# PCB0M3_2C.net
KiCad netlist of a schematic drawn in EAGLE
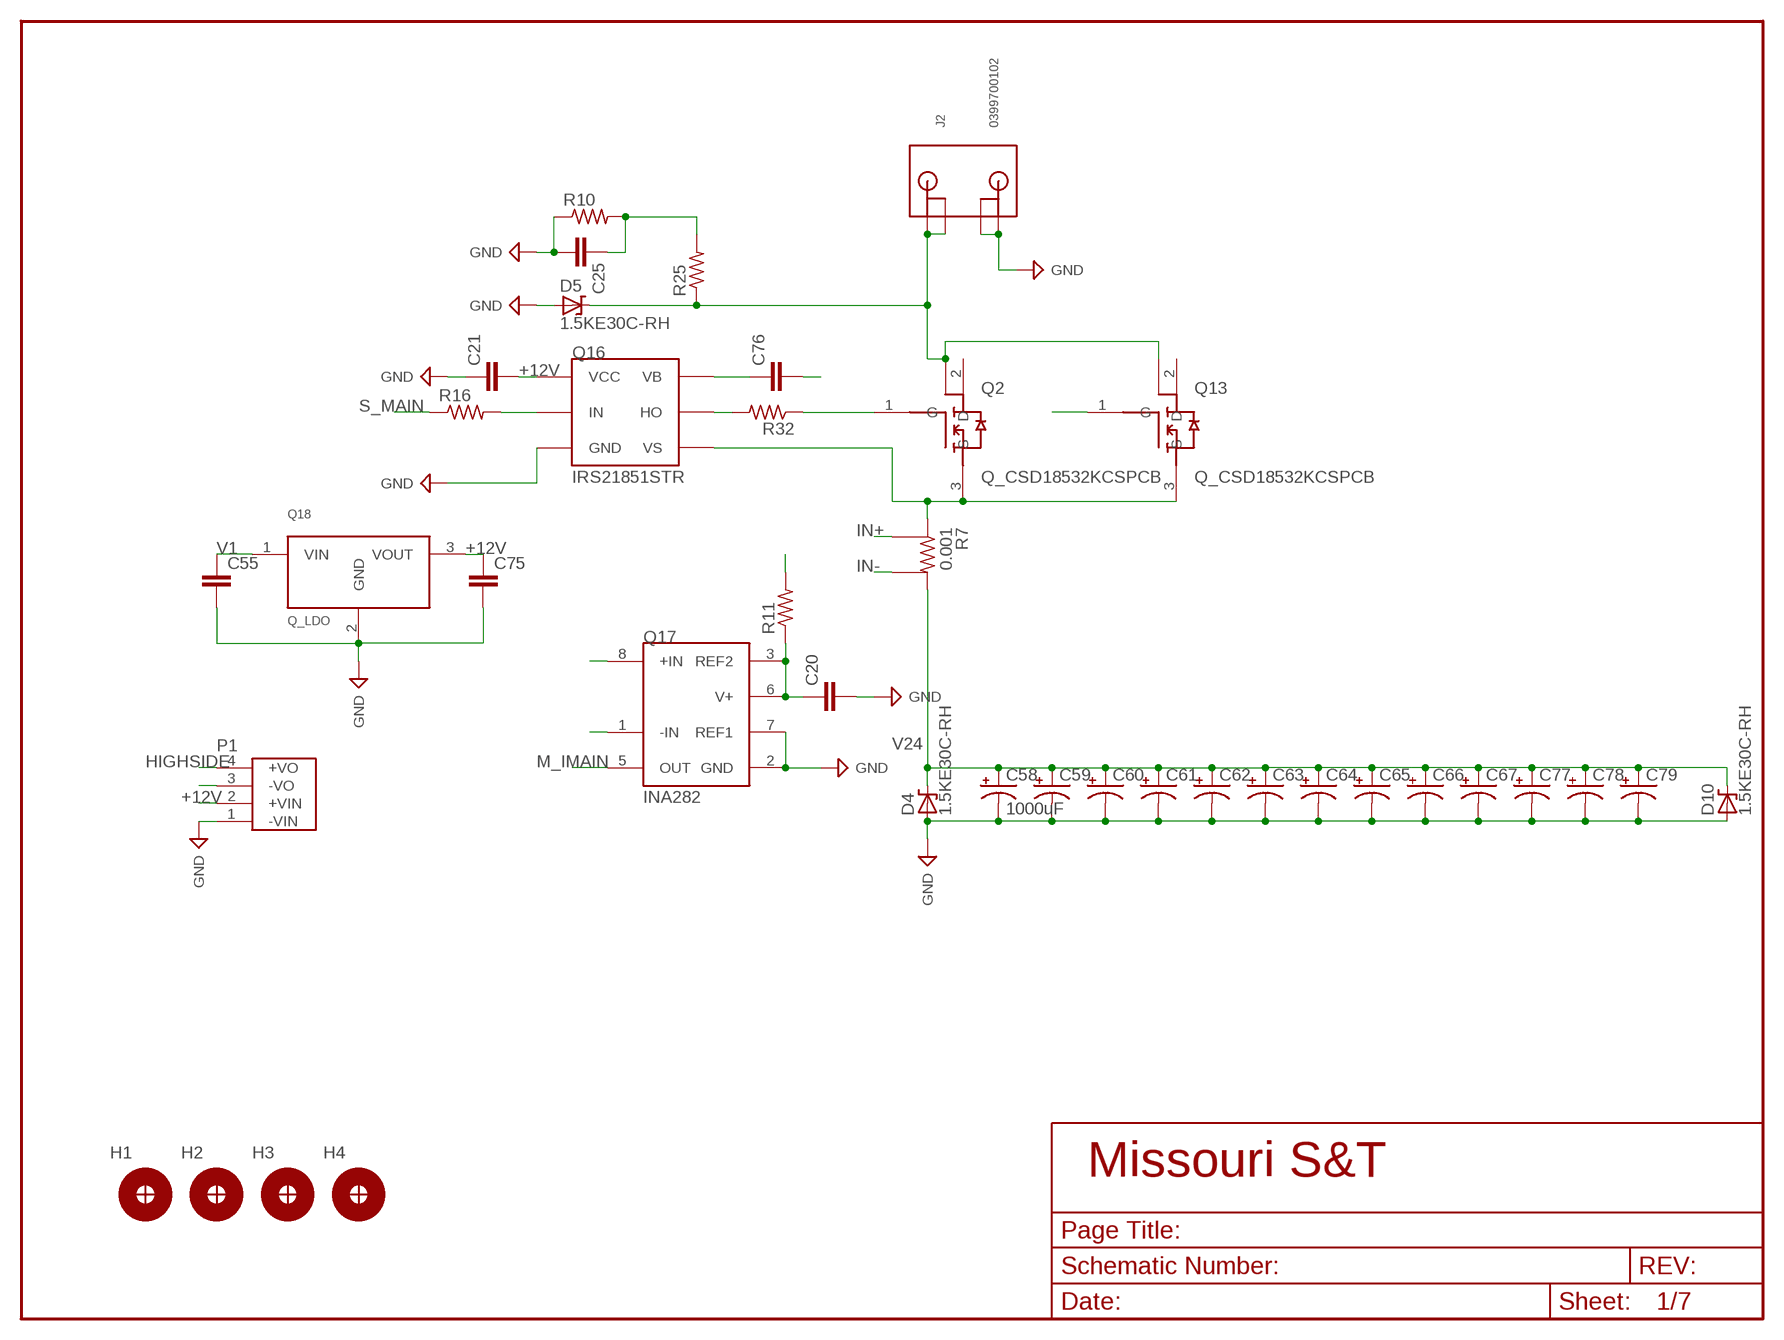
[diagram p0: schematic, sheet 1]
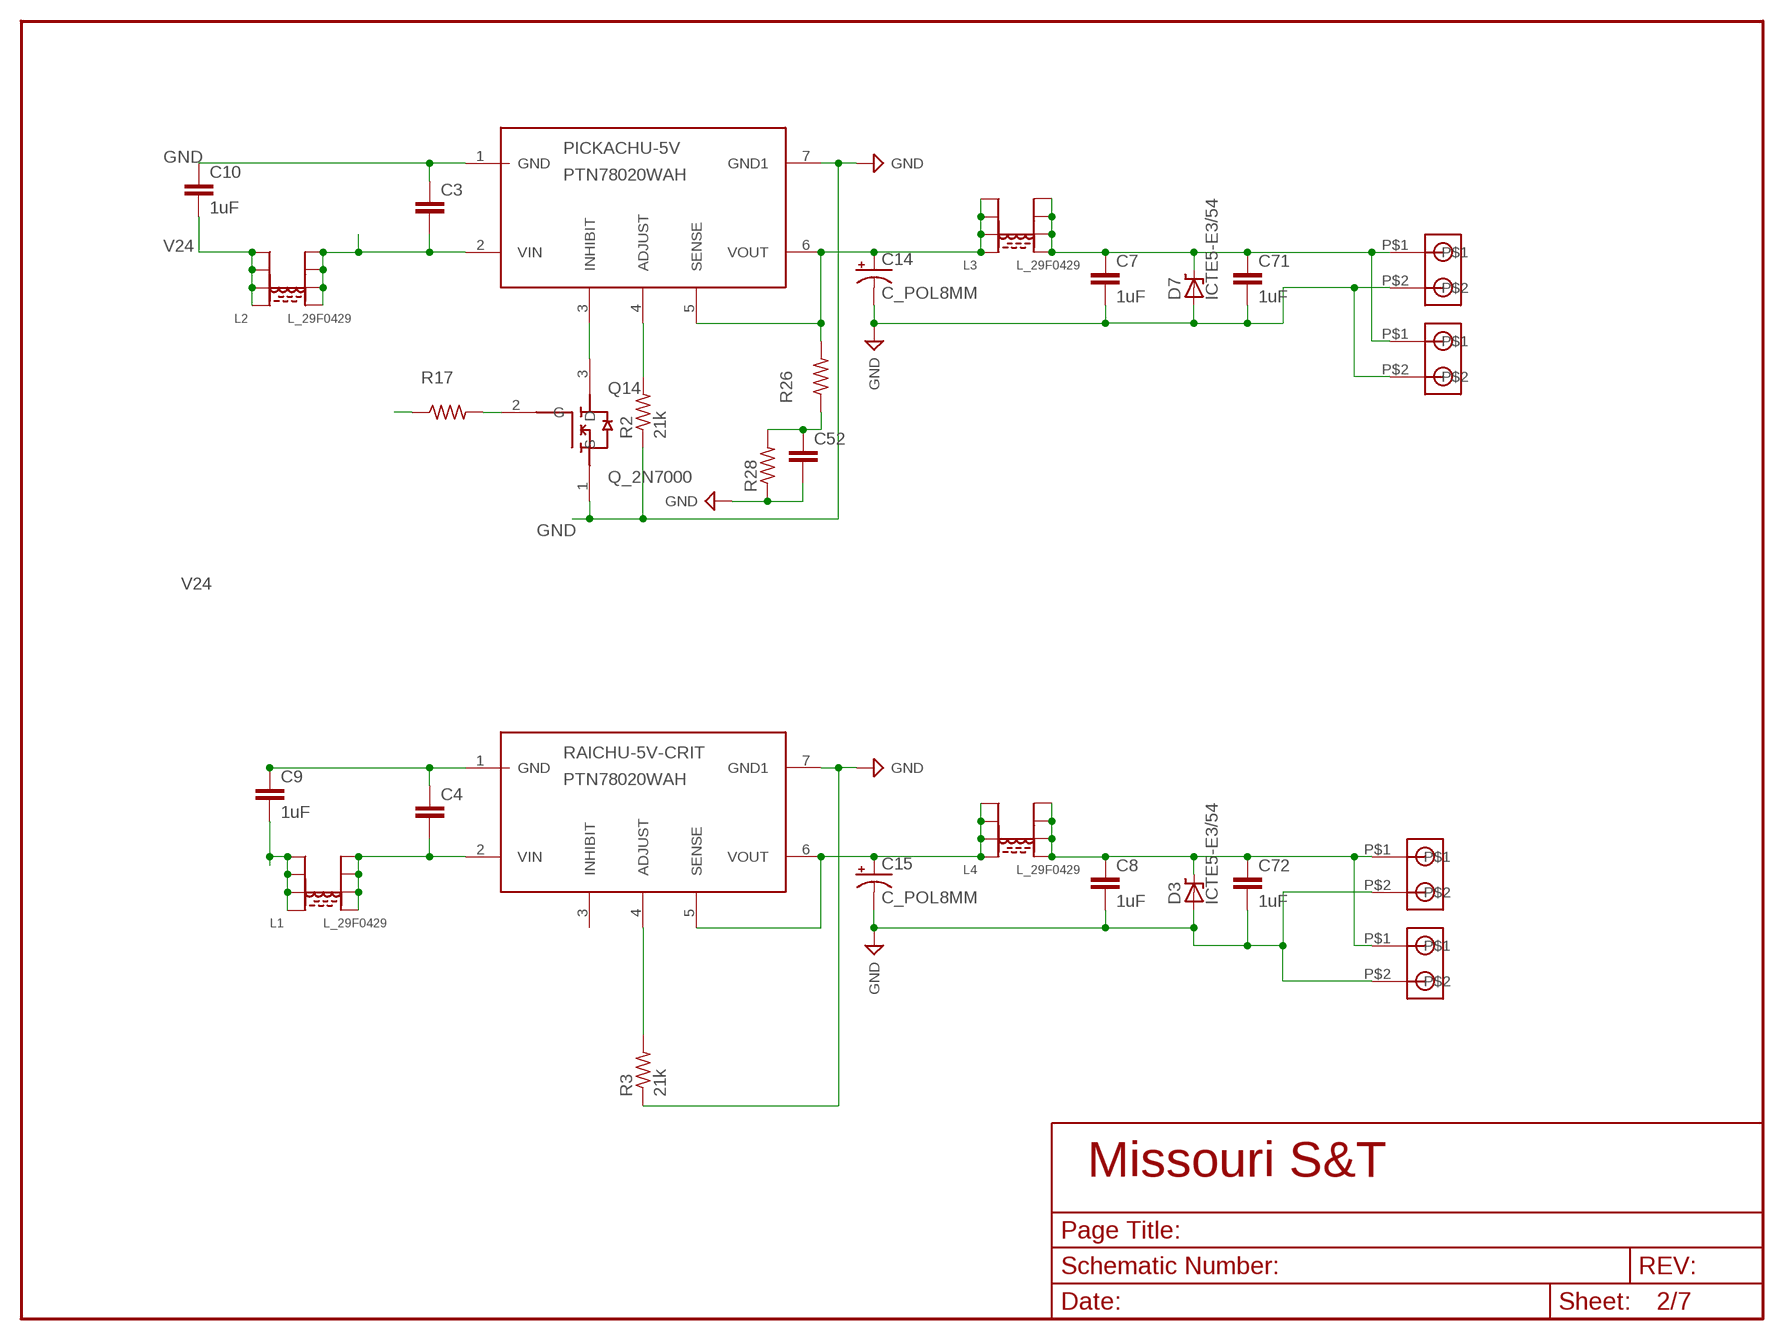
[diagram p1: schematic, sheet 2]
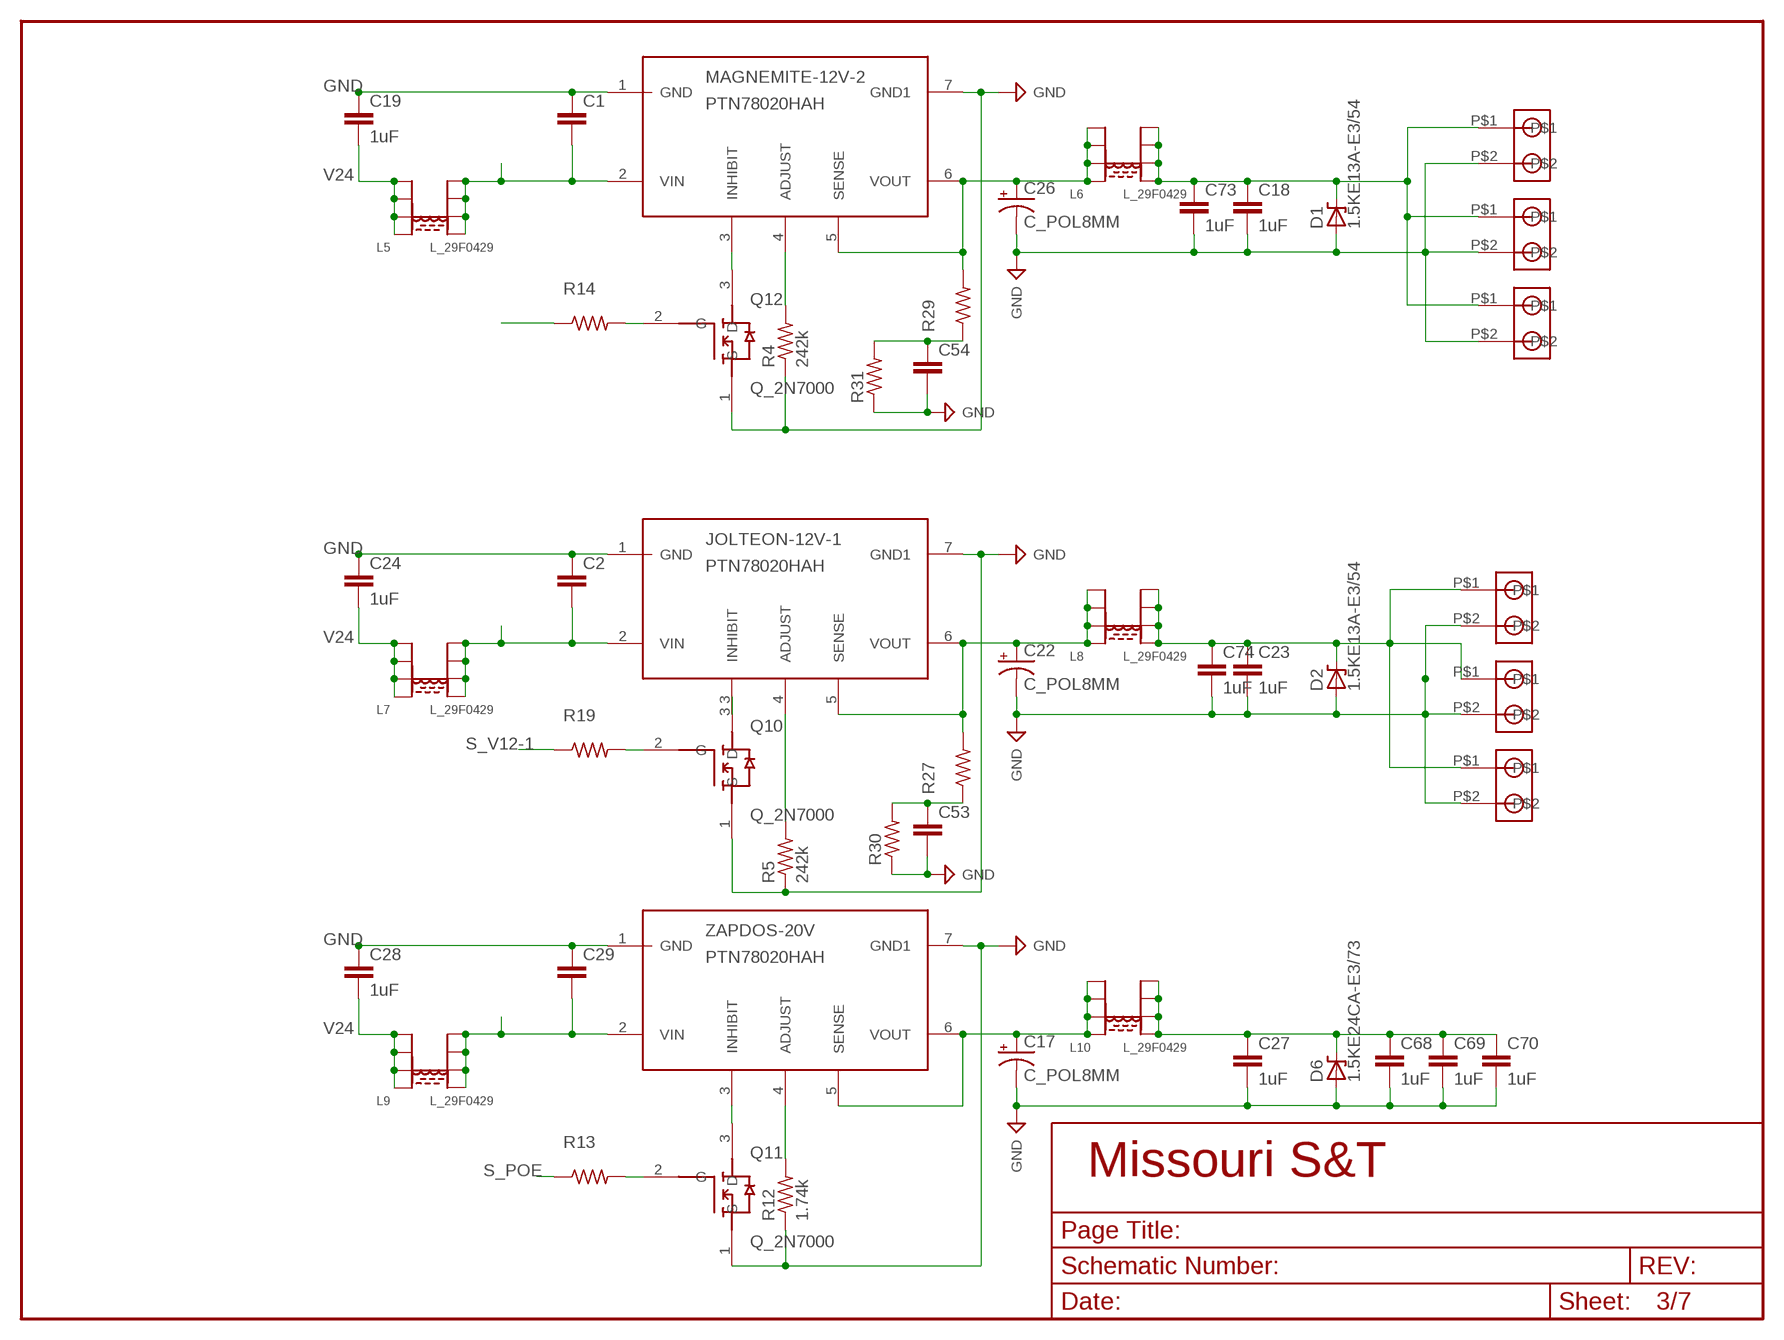
[diagram p2: schematic, sheet 3]
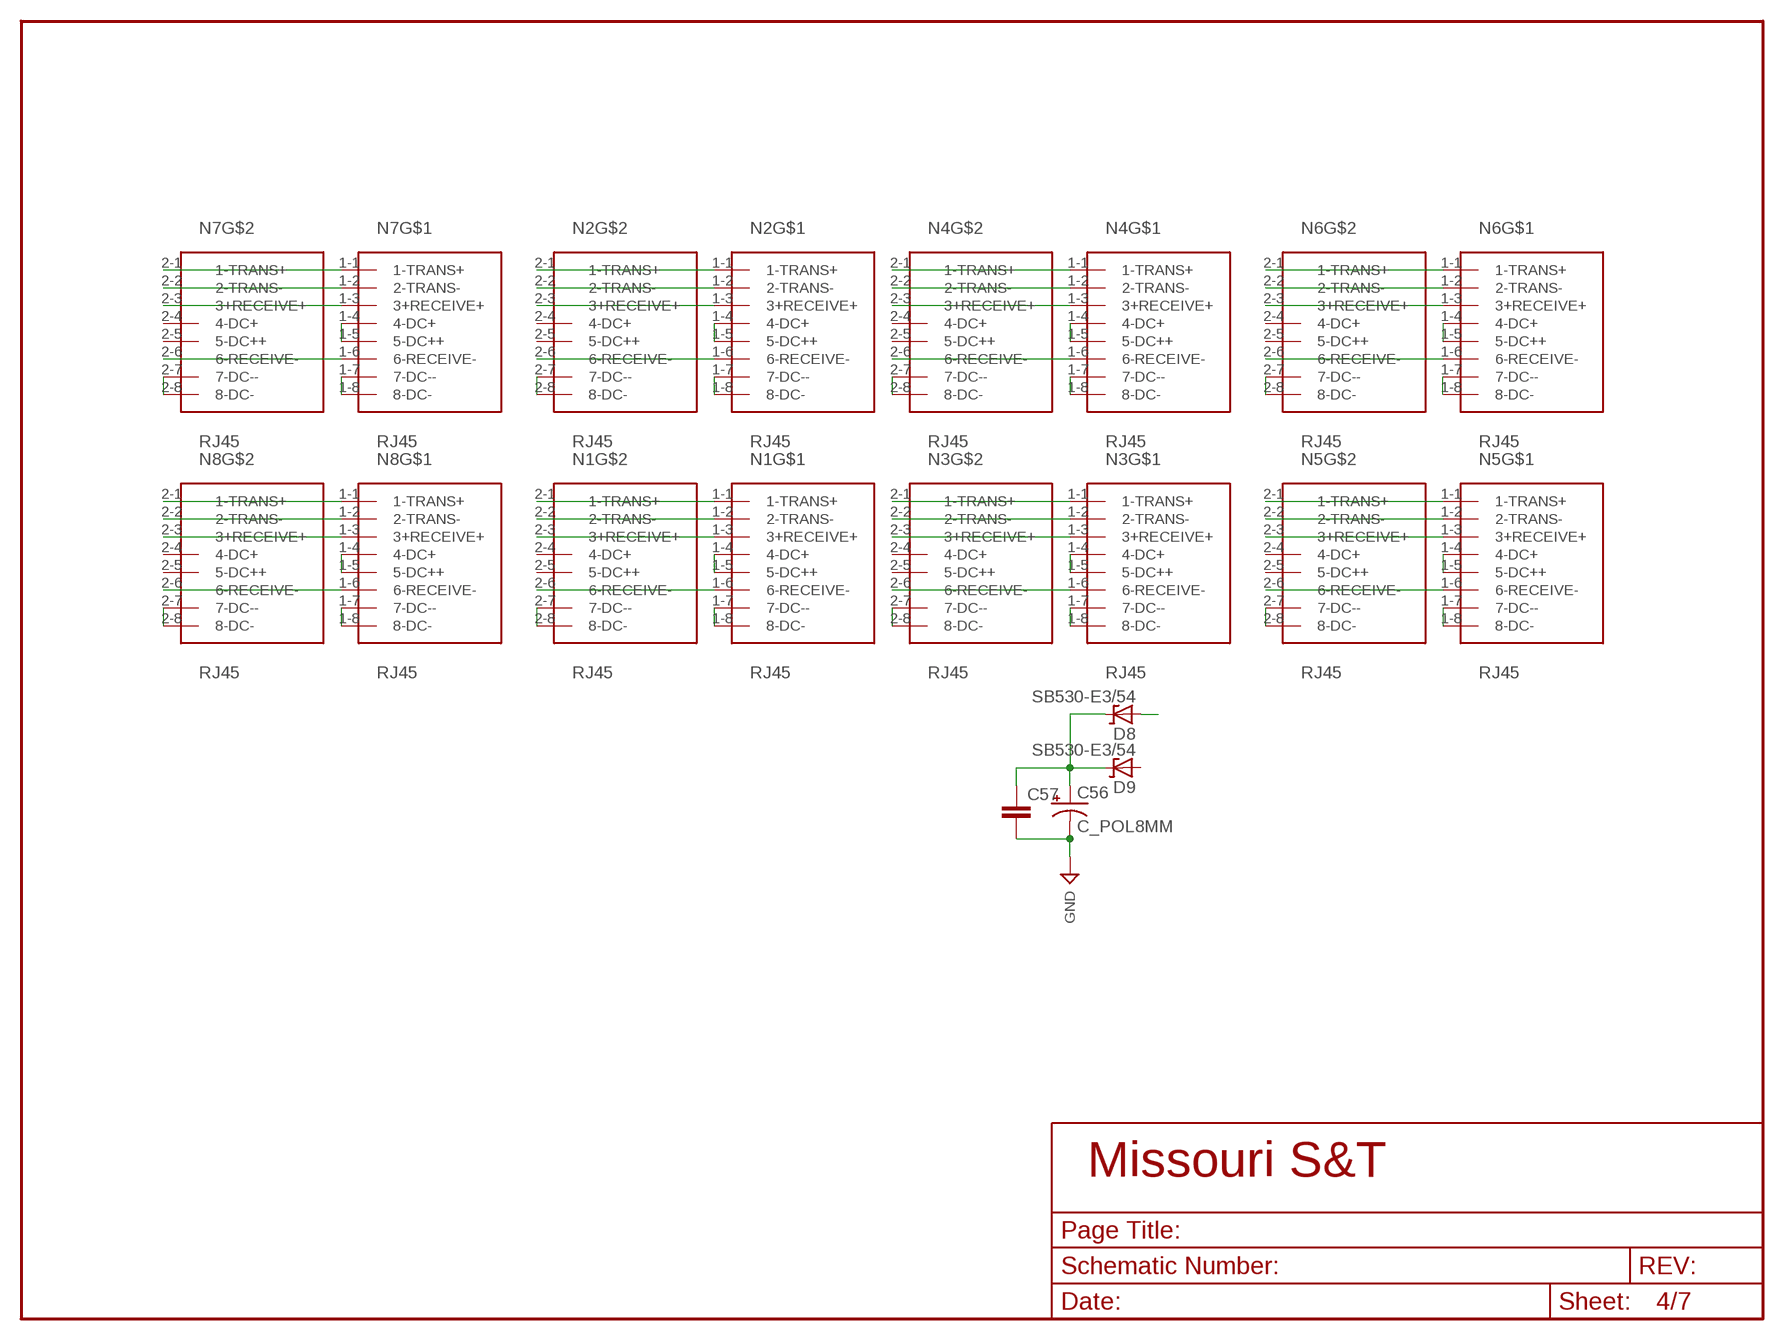
[diagram p3: schematic, sheet 4]
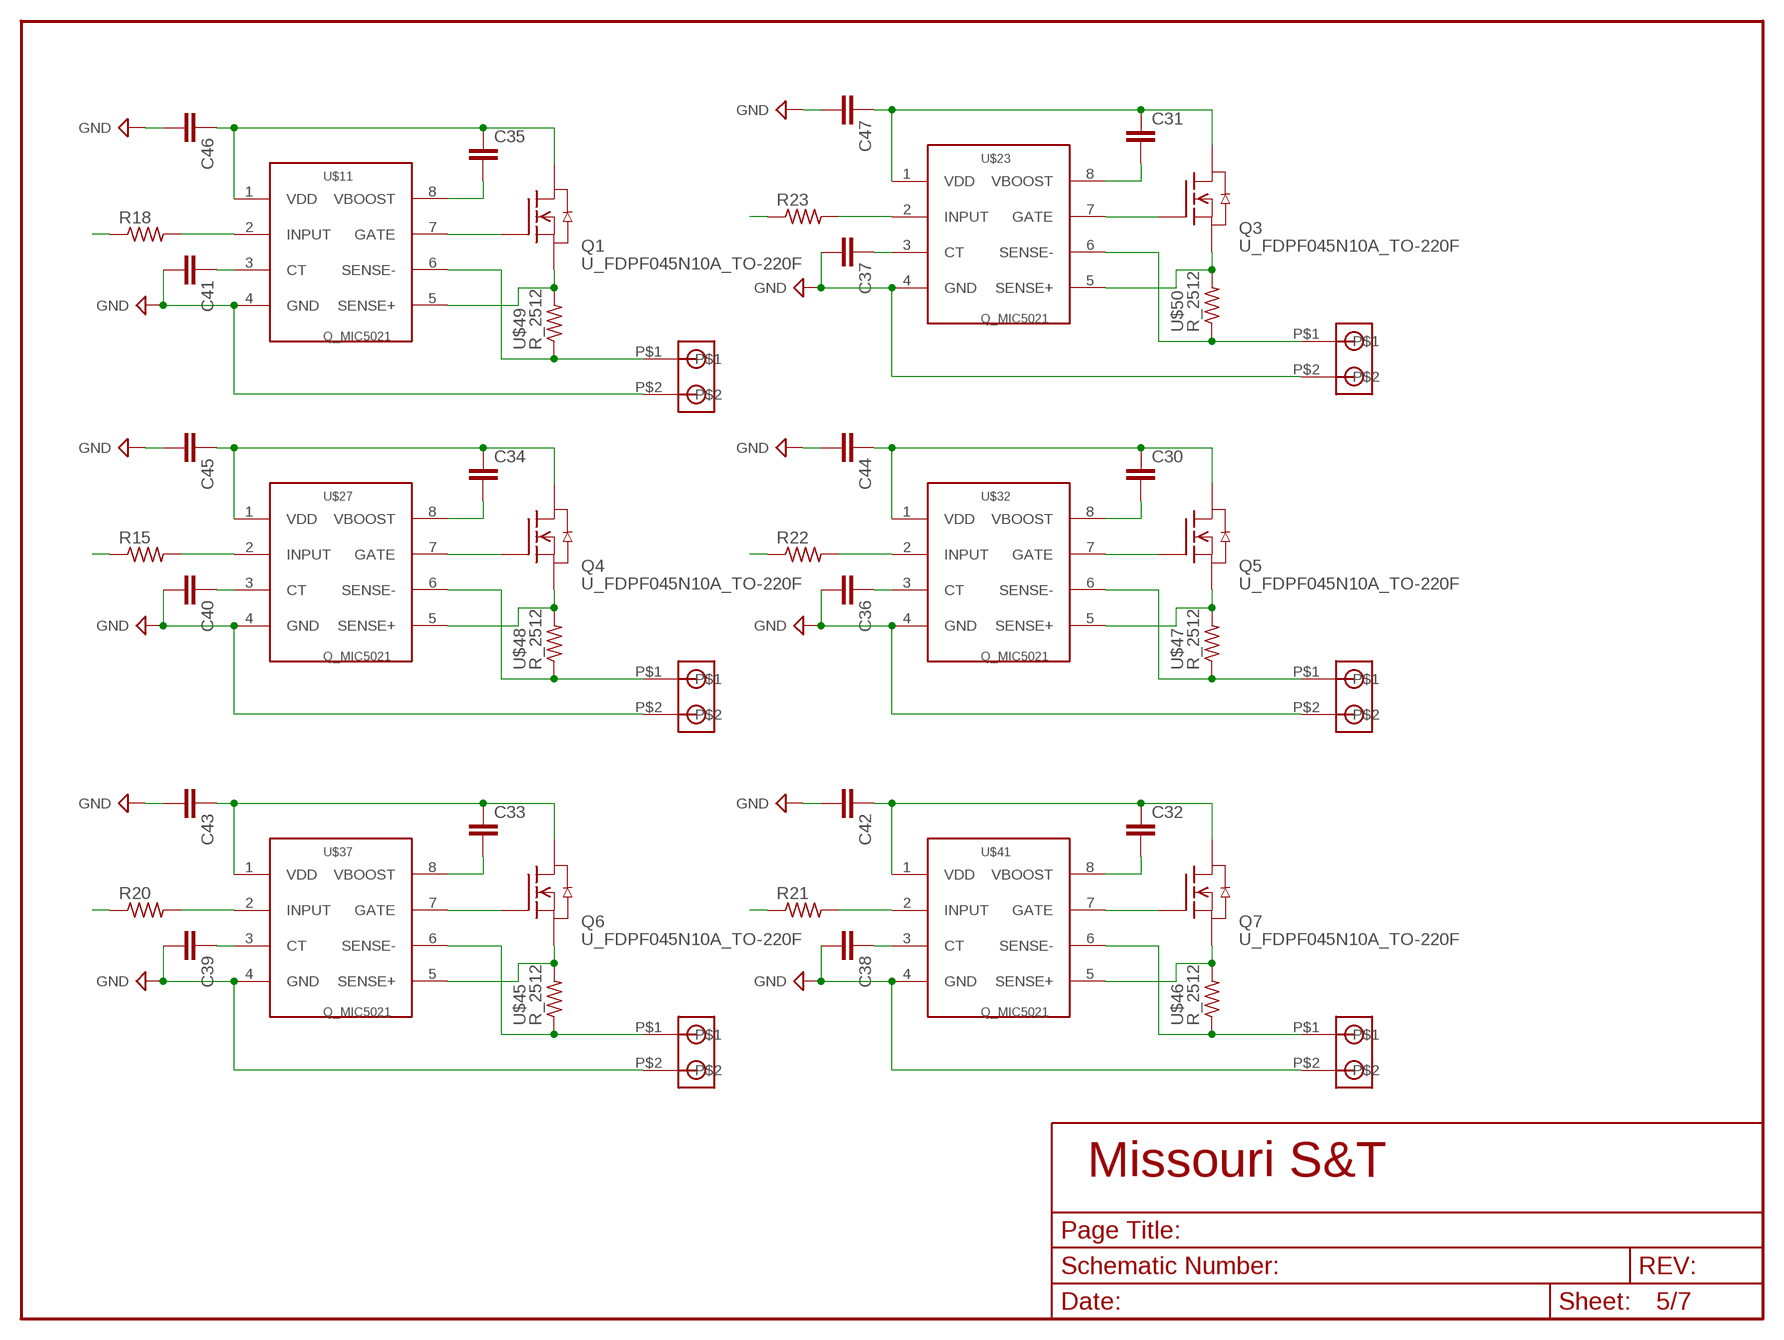
[diagram p4: schematic, sheet 5]
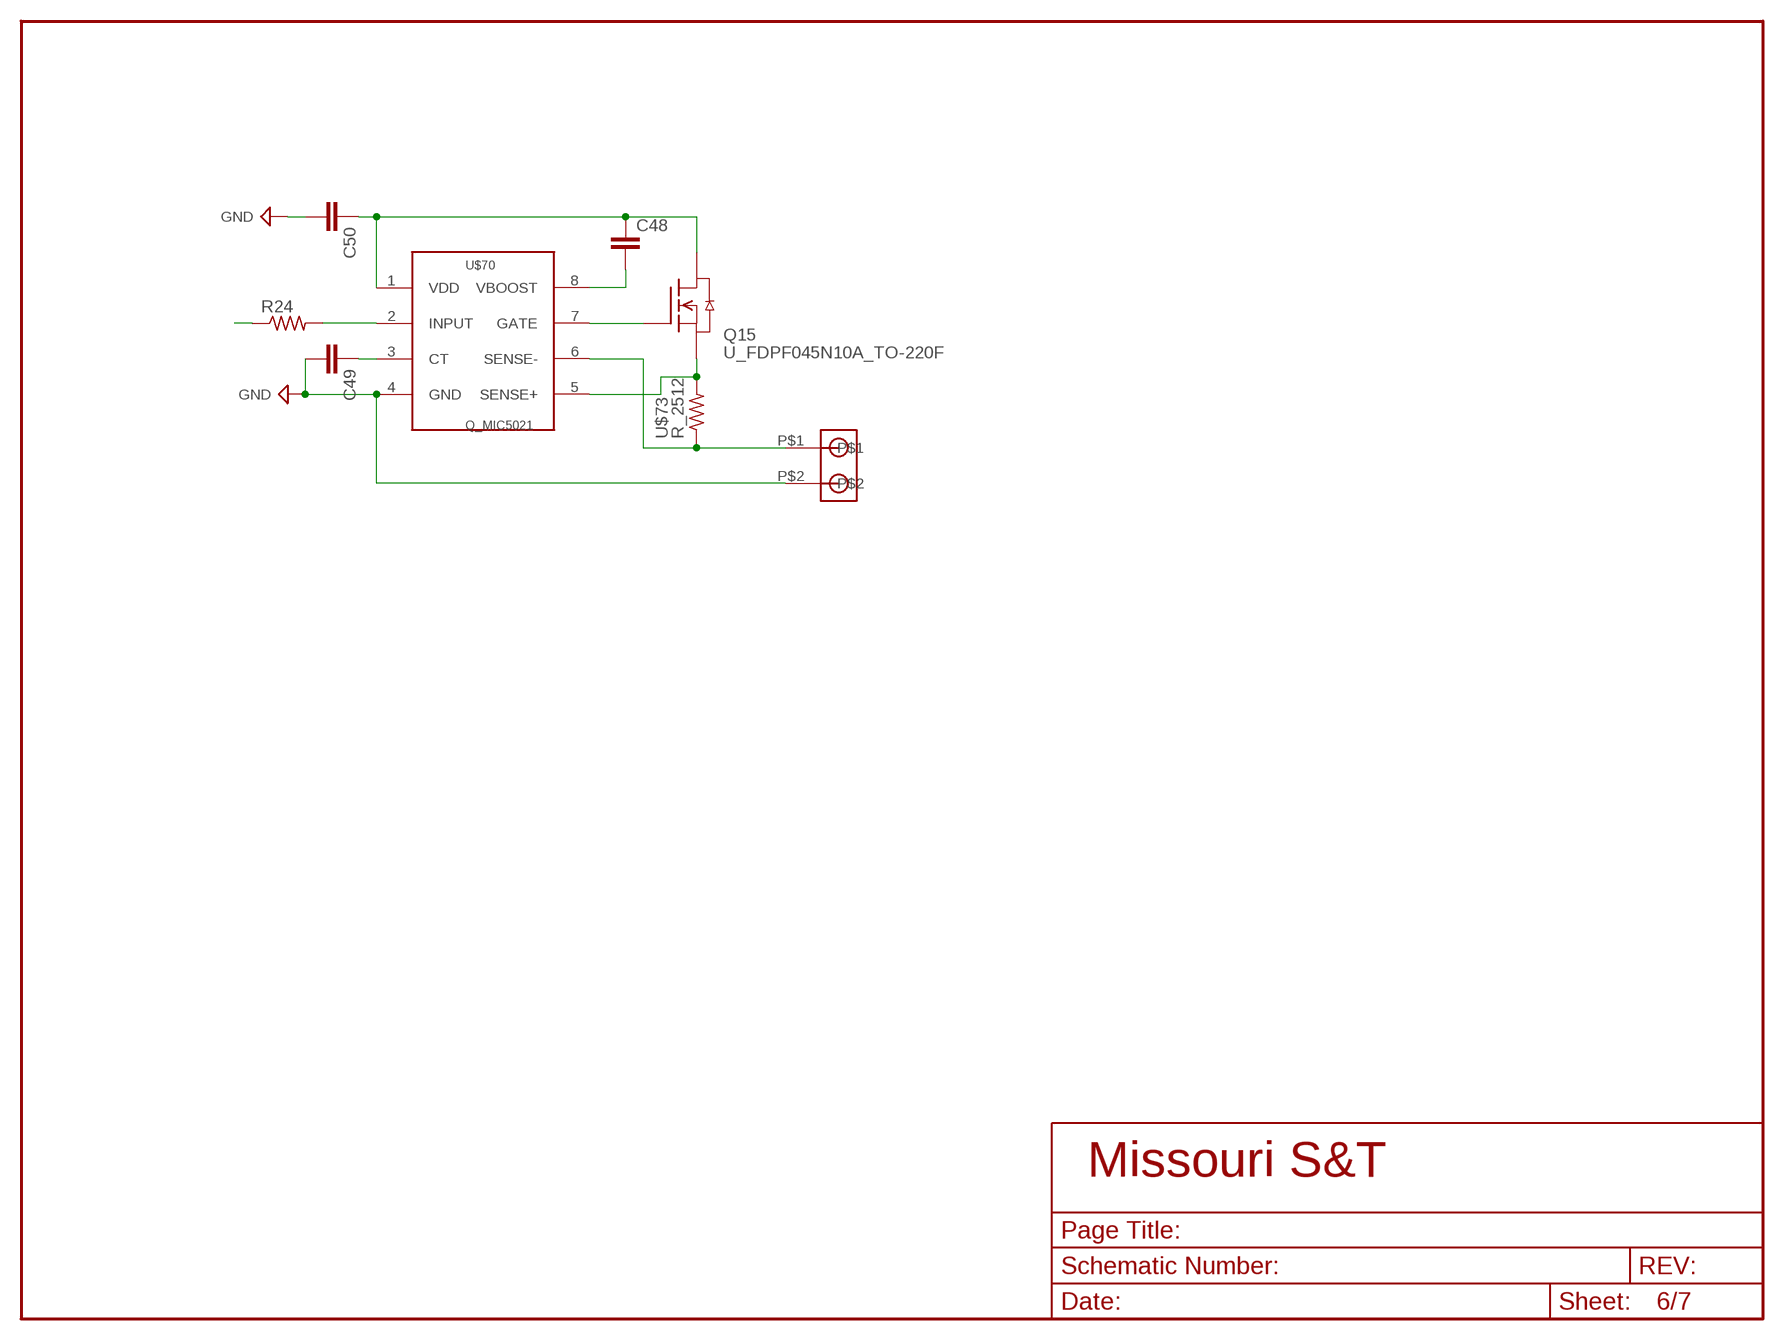
[diagram p5: schematic, sheet 6]
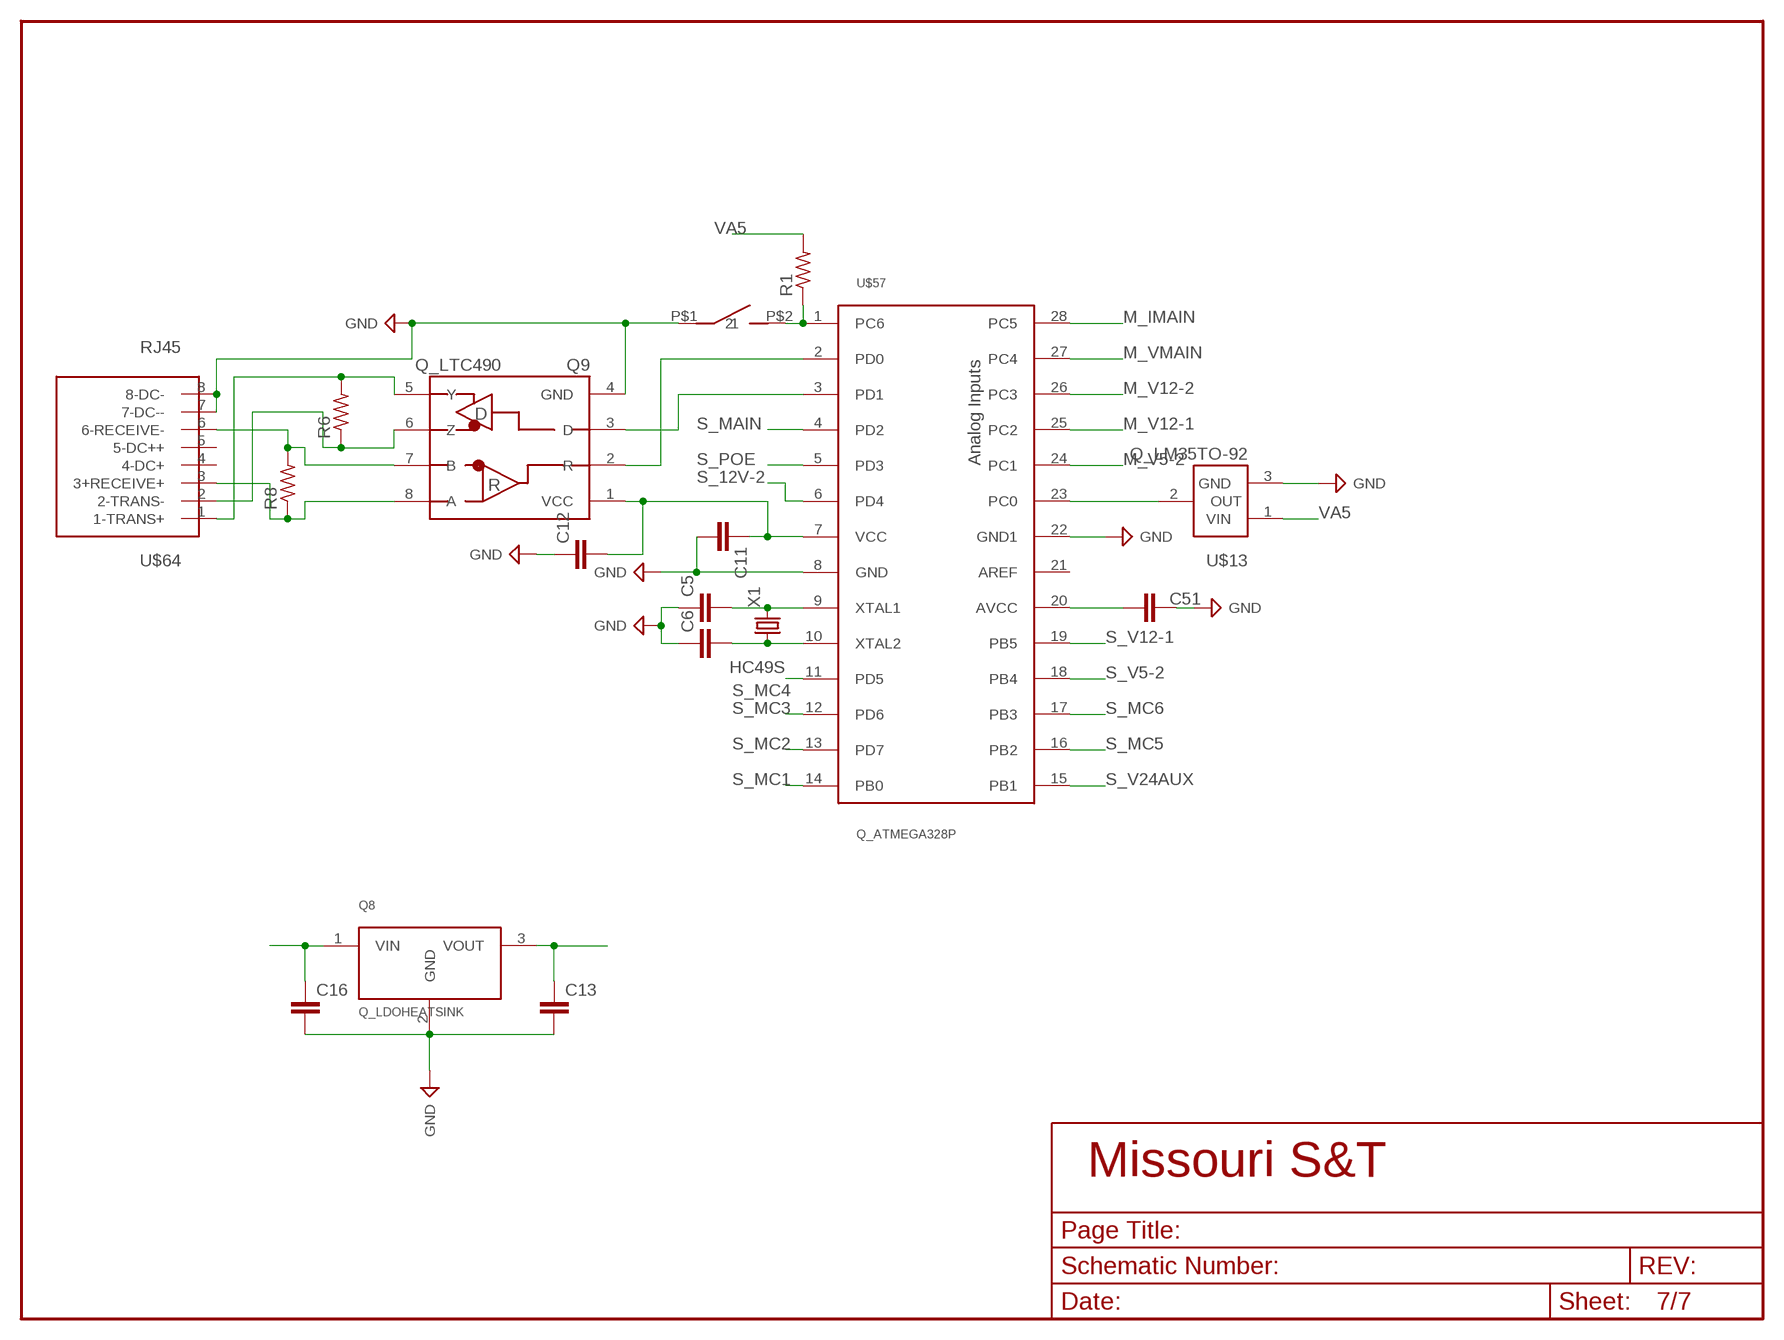
[diagram p6: schematic, sheet 7]

(export (version "E")
  (design (tool "Eeschema 10.0.6"))
  (components
    (comp (ref "C48")
      (value "C_CAP_1206")
      (footprint "eagle-import:C_1206")
      (libsource (lib "eagle-import") (part "C_CAP_1206"))
    )
    (comp (ref "C49")
      (value "C_CAP_1206")
      (footprint "eagle-import:C_1206")
      (libsource (lib "eagle-import") (part "C_CAP_1206"))
    )
    (comp (ref "C50")
      (value "C_CAP_1206")
      (footprint "eagle-import:C_1206")
      (libsource (lib "eagle-import") (part "C_CAP_1206"))
    )
    (comp (ref "Q15")
      (value "U_FDPF045N10A_TO-220F")
      (footprint "eagle-import:TO220F")
      (libsource (lib "eagle-import") (part "U_FDPF045N10A_TO-220F"))
    )
    (comp (ref "R24")
      (value "R_RES_1206")
      (footprint "eagle-import:R_1206")
      (libsource (lib "eagle-import") (part "R_RES_1206"))
    )
    (comp (ref "U$70")
      (value "Q_MIC5021")
      (footprint "eagle-import:DIP8")
      (libsource (lib "eagle-import") (part "Q_MIC5021"))
    )
    (comp (ref "U$72")
      (value "J_1546074-2")
      (footprint "eagle-import:THERM_BLOCK_2")
      (libsource (lib "eagle-import") (part "J_1546074-2"))
    )
    (comp (ref "U$73")
      (value "R_2512")
      (footprint "eagle-import:R_2512")
      (libsource (lib "eagle-import") (part "R_2512"))
    )
    (comp (ref "C3")
      (value "C_CAP_1206")
      (footprint "eagle-import:C_1206")
      (libsource (lib "eagle-import") (part "C_CAP_1206"))
    )
    (comp (ref "C4")
      (value "C_CAP_1206")
      (footprint "eagle-import:C_1206")
      (libsource (lib "eagle-import") (part "C_CAP_1206"))
    )
    (comp (ref "C7")
      (value "1uF")
      (footprint "eagle-import:C_1206")
      (libsource (lib "eagle-import") (part "C_CAP_1206"))
    )
    (comp (ref "C8")
      (value "1uF")
      (footprint "eagle-import:C_1206")
      (libsource (lib "eagle-import") (part "C_CAP_1206"))
    )
    (comp (ref "C9")
      (value "1uF")
      (footprint "eagle-import:C_1206")
      (libsource (lib "eagle-import") (part "C_CAP_1206"))
    )
    (comp (ref "C10")
      (value "1uF")
      (footprint "eagle-import:C_1206")
      (libsource (lib "eagle-import") (part "C_CAP_1206"))
    )
    (comp (ref "C14")
      (value "C_POL8MM")
      (footprint "eagle-import:C_8MM")
      (libsource (lib "eagle-import") (part "C_POL8MM"))
    )
    (comp (ref "C15")
      (value "C_POL8MM")
      (footprint "eagle-import:C_8MM")
      (libsource (lib "eagle-import") (part "C_POL8MM"))
    )
    (comp (ref "C52")
      (value "C_CAP_1206")
      (footprint "eagle-import:C_1206")
      (libsource (lib "eagle-import") (part "C_CAP_1206"))
    )
    (comp (ref "C71")
      (value "1uF")
      (footprint "eagle-import:C_1206")
      (libsource (lib "eagle-import") (part "C_CAP_1206"))
    )
    (comp (ref "C72")
      (value "1uF")
      (footprint "eagle-import:C_1206")
      (libsource (lib "eagle-import") (part "C_CAP_1206"))
    )
    (comp (ref "D3")
      (value "ICTE5-E3/54")
      (footprint "eagle-import:DIODE_D3.5MM_LS15.24MM")
      (libsource (lib "eagle-import") (part "D_1.5KE480A_D3.5MM_LS15.24MM"))
    )
    (comp (ref "D7")
      (value "ICTE5-E3/54")
      (footprint "eagle-import:DIODE_D3.5MM_LS15.24MM")
      (libsource (lib "eagle-import") (part "D_1.5KE480A_D3.5MM_LS15.24MM"))
    )
    (comp (ref "L1")
      (value "L_29F0429")
      (footprint "eagle-import:L_29F0429")
      (libsource (lib "eagle-import") (part "L_29F0429"))
    )
    (comp (ref "L2")
      (value "L_29F0429")
      (footprint "eagle-import:L_29F0429")
      (libsource (lib "eagle-import") (part "L_29F0429"))
    )
    (comp (ref "L3")
      (value "L_29F0429")
      (footprint "eagle-import:L_29F0429")
      (libsource (lib "eagle-import") (part "L_29F0429"))
    )
    (comp (ref "L4")
      (value "L_29F0429")
      (footprint "eagle-import:L_29F0429")
      (libsource (lib "eagle-import") (part "L_29F0429"))
    )
    (comp (ref "PICKACHU-5V")
      (value "PTN78020WAH")
      (footprint "eagle-import:R_PDSS-T7")
      (libsource (lib "eagle-import") (part "Q_PTN78020"))
    )
    (comp (ref "Q14")
      (value "Q_2N7000")
      (footprint "eagle-import:TO-92-3")
      (libsource (lib "eagle-import") (part "Q_2N7000"))
    )
    (comp (ref "R2")
      (value "21k")
      (footprint "eagle-import:R_1_4W")
      (libsource (lib "eagle-import") (part "R_1/4W"))
    )
    (comp (ref "R3")
      (value "21k")
      (footprint "eagle-import:R_1_4W")
      (libsource (lib "eagle-import") (part "R_1/4W"))
    )
    (comp (ref "R17")
      (value "R_1/4WL")
      (footprint "eagle-import:R_1_4WL")
      (libsource (lib "eagle-import") (part "R_1/4WL"))
    )
    (comp (ref "R26")
      (value "R_1/4WL")
      (footprint "eagle-import:R_1_4WL")
      (libsource (lib "eagle-import") (part "R_1/4WL"))
    )
    (comp (ref "R28")
      (value "R_RES_1206")
      (footprint "eagle-import:R_1206")
      (libsource (lib "eagle-import") (part "R_RES_1206"))
    )
    (comp (ref "RAICHU-5V-CRIT")
      (value "PTN78020WAH")
      (footprint "eagle-import:R_PDSS-T7")
      (libsource (lib "eagle-import") (part "Q_PTN78020"))
    )
    (comp (ref "U$52")
      (value "J_1546074-2282834-2")
      (footprint "eagle-import:J_2.54MM")
      (libsource (lib "eagle-import") (part "J_1546074-2282834-2"))
    )
    (comp (ref "U$53")
      (value "J_1546074-2282834-2")
      (footprint "eagle-import:J_2.54MM")
      (libsource (lib "eagle-import") (part "J_1546074-2282834-2"))
    )
    (comp (ref "U$54")
      (value "J_1546074-2282834-2")
      (footprint "eagle-import:J_2.54MM")
      (libsource (lib "eagle-import") (part "J_1546074-2282834-2"))
    )
    (comp (ref "U$55")
      (value "J_1546074-2282834-2")
      (footprint "eagle-import:J_2.54MM")
      (libsource (lib "eagle-import") (part "J_1546074-2282834-2"))
    )
    (comp (ref "C5")
      (value "C_CAP_1206")
      (footprint "eagle-import:C_1206")
      (libsource (lib "eagle-import") (part "C_CAP_1206"))
    )
    (comp (ref "C6")
      (value "C_CAP_1206")
      (footprint "eagle-import:C_1206")
      (libsource (lib "eagle-import") (part "C_CAP_1206"))
    )
    (comp (ref "C11")
      (value "C_CAP_1206")
      (footprint "eagle-import:C_1206")
      (libsource (lib "eagle-import") (part "C_CAP_1206"))
    )
    (comp (ref "C12")
      (value "C_CAP_1206")
      (footprint "eagle-import:C_1206")
      (libsource (lib "eagle-import") (part "C_CAP_1206"))
    )
    (comp (ref "C13")
      (value "C_CAP_1206")
      (footprint "eagle-import:C_1206")
      (libsource (lib "eagle-import") (part "C_CAP_1206"))
    )
    (comp (ref "C16")
      (value "C_CAP_1206")
      (footprint "eagle-import:C_1206")
      (libsource (lib "eagle-import") (part "C_CAP_1206"))
    )
    (comp (ref "C51")
      (value "C_CAP_1206")
      (footprint "eagle-import:C_1206")
      (libsource (lib "eagle-import") (part "C_CAP_1206"))
    )
    (comp (ref "J1")
      (value "J_MC32857")
      (footprint "eagle-import:J_TOGGLE")
      (libsource (lib "eagle-import") (part "J_MC32857"))
    )
    (comp (ref "Q8")
      (value "Q_LDOHEATSINK")
      (footprint "eagle-import:TO220_6025DG")
      (libsource (lib "eagle-import") (part "Q_LDOHEATSINK"))
    )
    (comp (ref "Q9")
      (value "Q_LTC490")
      (footprint "eagle-import:DIP8")
      (libsource (lib "eagle-import") (part "Q_LTC490"))
    )
    (comp (ref "R1")
      (value "R_RES_1206")
      (footprint "eagle-import:R_1206")
      (libsource (lib "eagle-import") (part "R_RES_1206"))
    )
    (comp (ref "R6")
      (value "R_RES_1206")
      (footprint "eagle-import:R_1206")
      (libsource (lib "eagle-import") (part "R_RES_1206"))
    )
    (comp (ref "R8")
      (value "R_RES_1206")
      (footprint "eagle-import:R_1206")
      (libsource (lib "eagle-import") (part "R_RES_1206"))
    )
    (comp (ref "U$13")
      (value "Q_LM35TO-92")
      (footprint "eagle-import:TO-92-3")
      (libsource (lib "eagle-import") (part "Q_LM35TO-92"))
    )
    (comp (ref "U$57")
      (value "Q_ATMEGA328P")
      (footprint "eagle-import:DIP28")
      (libsource (lib "eagle-import") (part "Q_ATMEGA328P"))
    )
    (comp (ref "U$64")
      (value "RJ45")
      (footprint "eagle-import:RJ45-CAT5E")
      (libsource (lib "eagle-import") (part "RJ45"))
    )
    (comp (ref "X1")
      (value "HC49S")
      (footprint "eagle-import:HC-49")
      (libsource (lib "eagle-import") (part "X_HC49SCRYSTAL"))
    )
    (comp (ref "C56")
      (value "C_POL8MM")
      (footprint "eagle-import:C_8MM")
      (libsource (lib "eagle-import") (part "C_POL8MM"))
    )
    (comp (ref "C57")
      (value "C_CAP_1206")
      (footprint "eagle-import:C_1206")
      (libsource (lib "eagle-import") (part "C_CAP_1206"))
    )
    (comp (ref "D8")
      (value "SB530-E3/54")
      (footprint "eagle-import:DIODE_D3.5MM_LS15.24MM")
      (libsource (lib "eagle-import") (part "D_1.5KE480A_D3.5MM_LS15.24MM"))
    )
    (comp (ref "D9")
      (value "SB530-E3/54")
      (footprint "eagle-import:DIODE_D3.5MM_LS15.24MM")
      (libsource (lib "eagle-import") (part "D_1.5KE480A_D3.5MM_LS15.24MM"))
    )
    (comp (ref "N1")
      (value "RJ45")
      (footprint "eagle-import:RJ45-CAT5E-2PACK")
      (libsource (lib "eagle-import") (part "RJ45-2PORT"))
    )
    (comp (ref "N2")
      (value "RJ45")
      (footprint "eagle-import:RJ45-CAT5E-2PACK")
      (libsource (lib "eagle-import") (part "RJ45-2PORT"))
    )
    (comp (ref "N3")
      (value "RJ45")
      (footprint "eagle-import:RJ45-CAT5E-2PACK")
      (libsource (lib "eagle-import") (part "RJ45-2PORT"))
    )
    (comp (ref "N4")
      (value "RJ45")
      (footprint "eagle-import:RJ45-CAT5E-2PACK")
      (libsource (lib "eagle-import") (part "RJ45-2PORT"))
    )
    (comp (ref "N5")
      (value "RJ45")
      (footprint "eagle-import:RJ45-CAT5E-2PACK")
      (libsource (lib "eagle-import") (part "RJ45-2PORT"))
    )
    (comp (ref "N6")
      (value "RJ45")
      (footprint "eagle-import:RJ45-CAT5E-2PACK")
      (libsource (lib "eagle-import") (part "RJ45-2PORT"))
    )
    (comp (ref "N7")
      (value "RJ45")
      (footprint "eagle-import:RJ45-CAT5E-2PACK")
      (libsource (lib "eagle-import") (part "RJ45-2PORT"))
    )
    (comp (ref "N8")
      (value "RJ45")
      (footprint "eagle-import:RJ45-CAT5E-2PACK")
      (libsource (lib "eagle-import") (part "RJ45-2PORT"))
    )
    (comp (ref "C1")
      (value "C_CAP_1206")
      (footprint "eagle-import:C_1206")
      (libsource (lib "eagle-import") (part "C_CAP_1206"))
    )
    (comp (ref "C2")
      (value "C_CAP_1206")
      (footprint "eagle-import:C_1206")
      (libsource (lib "eagle-import") (part "C_CAP_1206"))
    )
    (comp (ref "C17")
      (value "C_POL8MM")
      (footprint "eagle-import:C_8MM")
      (libsource (lib "eagle-import") (part "C_POL8MM"))
    )
    (comp (ref "C18")
      (value "1uF")
      (footprint "eagle-import:C_1206")
      (libsource (lib "eagle-import") (part "C_CAP_1206"))
    )
    (comp (ref "C19")
      (value "1uF")
      (footprint "eagle-import:C_1206")
      (libsource (lib "eagle-import") (part "C_CAP_1206"))
    )
    (comp (ref "C22")
      (value "C_POL8MM")
      (footprint "eagle-import:C_8MM")
      (libsource (lib "eagle-import") (part "C_POL8MM"))
    )
    (comp (ref "C23")
      (value "1uF")
      (footprint "eagle-import:C_1206")
      (libsource (lib "eagle-import") (part "C_CAP_1206"))
    )
    (comp (ref "C24")
      (value "1uF")
      (footprint "eagle-import:C_1206")
      (libsource (lib "eagle-import") (part "C_CAP_1206"))
    )
    (comp (ref "C26")
      (value "C_POL8MM")
      (footprint "eagle-import:C_8MM")
      (libsource (lib "eagle-import") (part "C_POL8MM"))
    )
    (comp (ref "C27")
      (value "1uF")
      (footprint "eagle-import:C_1206")
      (libsource (lib "eagle-import") (part "C_CAP_1206"))
    )
    (comp (ref "C28")
      (value "1uF")
      (footprint "eagle-import:C_1206")
      (libsource (lib "eagle-import") (part "C_CAP_1206"))
    )
    (comp (ref "C29")
      (value "C_CAP_1206")
      (footprint "eagle-import:C_1206")
      (libsource (lib "eagle-import") (part "C_CAP_1206"))
    )
    (comp (ref "C53")
      (value "C_CAP_1206")
      (footprint "eagle-import:C_1206")
      (libsource (lib "eagle-import") (part "C_CAP_1206"))
    )
    (comp (ref "C54")
      (value "C_CAP_1206")
      (footprint "eagle-import:C_1206")
      (libsource (lib "eagle-import") (part "C_CAP_1206"))
    )
    (comp (ref "C68")
      (value "1uF")
      (footprint "eagle-import:C_1206")
      (libsource (lib "eagle-import") (part "C_CAP_1206"))
    )
    (comp (ref "C69")
      (value "1uF")
      (footprint "eagle-import:C_1206")
      (libsource (lib "eagle-import") (part "C_CAP_1206"))
    )
    (comp (ref "C70")
      (value "1uF")
      (footprint "eagle-import:C_1206")
      (libsource (lib "eagle-import") (part "C_CAP_1206"))
    )
    (comp (ref "C73")
      (value "1uF")
      (footprint "eagle-import:C_1206")
      (libsource (lib "eagle-import") (part "C_CAP_1206"))
    )
    (comp (ref "C74")
      (value "1uF")
      (footprint "eagle-import:C_1206")
      (libsource (lib "eagle-import") (part "C_CAP_1206"))
    )
    (comp (ref "D1")
      (value "1.5KE13A-E3/54")
      (footprint "eagle-import:DIODE_D3.5MM_LS15.24MM")
      (libsource (lib "eagle-import") (part "D_1.5KE480A_D3.5MM_LS15.24MM"))
    )
    (comp (ref "D2")
      (value "1.5KE13A-E3/54")
      (footprint "eagle-import:DIODE_D3.5MM_LS15.24MM")
      (libsource (lib "eagle-import") (part "D_1.5KE480A_D3.5MM_LS15.24MM"))
    )
    (comp (ref "D6")
      (value "1.5KE24CA-E3/73")
      (footprint "eagle-import:DIODE_D3.5MM_LS15.24MM")
      (libsource (lib "eagle-import") (part "D_1.5KE480A_D3.5MM_LS15.24MM"))
    )
    (comp (ref "J3")
      (value "J_1546074-2282834-2")
      (footprint "eagle-import:J_2.54MM")
      (libsource (lib "eagle-import") (part "J_1546074-2282834-2"))
    )
    (comp (ref "J4")
      (value "J_1546074-2282834-2")
      (footprint "eagle-import:J_2.54MM")
      (libsource (lib "eagle-import") (part "J_1546074-2282834-2"))
    )
    (comp (ref "J5")
      (value "J_1546074-2282834-2")
      (footprint "eagle-import:J_2.54MM")
      (libsource (lib "eagle-import") (part "J_1546074-2282834-2"))
    )
    (comp (ref "J6")
      (value "J_1546074-2282834-2")
      (footprint "eagle-import:J_2.54MM")
      (libsource (lib "eagle-import") (part "J_1546074-2282834-2"))
    )
    (comp (ref "J7")
      (value "J_1546074-2282834-2")
      (footprint "eagle-import:J_2.54MM")
      (libsource (lib "eagle-import") (part "J_1546074-2282834-2"))
    )
    (comp (ref "J8")
      (value "J_1546074-2282834-2")
      (footprint "eagle-import:J_2.54MM")
      (libsource (lib "eagle-import") (part "J_1546074-2282834-2"))
    )
    (comp (ref "JOLTEON-12V-1")
      (value "PTN78020HAH")
      (footprint "eagle-import:R_PDSS-T7")
      (libsource (lib "eagle-import") (part "Q_PTN78020"))
    )
    (comp (ref "L5")
      (value "L_29F0429")
      (footprint "eagle-import:L_29F0429")
      (libsource (lib "eagle-import") (part "L_29F0429"))
    )
    (comp (ref "L6")
      (value "L_29F0429")
      (footprint "eagle-import:L_29F0429")
      (libsource (lib "eagle-import") (part "L_29F0429"))
    )
    (comp (ref "L7")
      (value "L_29F0429")
      (footprint "eagle-import:L_29F0429")
      (libsource (lib "eagle-import") (part "L_29F0429"))
    )
    (comp (ref "L8")
      (value "L_29F0429")
      (footprint "eagle-import:L_29F0429")
      (libsource (lib "eagle-import") (part "L_29F0429"))
    )
    (comp (ref "L9")
      (value "L_29F0429")
      (footprint "eagle-import:L_29F0429")
      (libsource (lib "eagle-import") (part "L_29F0429"))
    )
    (comp (ref "L10")
      (value "L_29F0429")
      (footprint "eagle-import:L_29F0429")
      (libsource (lib "eagle-import") (part "L_29F0429"))
    )
    (comp (ref "MAGNEMITE-12V-2")
      (value "PTN78020HAH")
      (footprint "eagle-import:R_PDSS-T7")
      (libsource (lib "eagle-import") (part "Q_PTN78020"))
    )
    (comp (ref "Q10")
      (value "Q_2N7000")
      (footprint "eagle-import:TO-92-3")
      (libsource (lib "eagle-import") (part "Q_2N7000"))
    )
    (comp (ref "Q11")
      (value "Q_2N7000")
      (footprint "eagle-import:TO-92-3")
      (libsource (lib "eagle-import") (part "Q_2N7000"))
    )
    (comp (ref "Q12")
      (value "Q_2N7000")
      (footprint "eagle-import:TO-92-3")
      (libsource (lib "eagle-import") (part "Q_2N7000"))
    )
    (comp (ref "R4")
      (value "242k")
      (footprint "eagle-import:R_1_4W")
      (libsource (lib "eagle-import") (part "R_1/4W"))
    )
    (comp (ref "R5")
      (value "242k")
      (footprint "eagle-import:R_1_4W")
      (libsource (lib "eagle-import") (part "R_1/4W"))
    )
    (comp (ref "R12")
      (value "1.74k")
      (footprint "eagle-import:R_1_4W")
      (libsource (lib "eagle-import") (part "R_1/4W"))
    )
    (comp (ref "R13")
      (value "R_1/4WL")
      (footprint "eagle-import:R_1_4WL")
      (libsource (lib "eagle-import") (part "R_1/4WL"))
    )
    (comp (ref "R14")
      (value "R_1/4WL")
      (footprint "eagle-import:R_1_4WL")
      (libsource (lib "eagle-import") (part "R_1/4WL"))
    )
    (comp (ref "R19")
      (value "R_1/4WL")
      (footprint "eagle-import:R_1_4WL")
      (libsource (lib "eagle-import") (part "R_1/4WL"))
    )
    (comp (ref "R27")
      (value "R_1/4WL")
      (footprint "eagle-import:R_1_4WL")
      (libsource (lib "eagle-import") (part "R_1/4WL"))
    )
    (comp (ref "R29")
      (value "R_1/4WL")
      (footprint "eagle-import:R_1_4WL")
      (libsource (lib "eagle-import") (part "R_1/4WL"))
    )
    (comp (ref "R30")
      (value "R_RES_1206")
      (footprint "eagle-import:R_1206")
      (libsource (lib "eagle-import") (part "R_RES_1206"))
    )
    (comp (ref "R31")
      (value "R_RES_1206")
      (footprint "eagle-import:R_1206")
      (libsource (lib "eagle-import") (part "R_RES_1206"))
    )
    (comp (ref "ZAPDOS-20V")
      (value "PTN78020HAH")
      (footprint "eagle-import:R_PDSS-T7")
      (libsource (lib "eagle-import") (part "Q_PTN78020"))
    )
    (comp (ref "C30")
      (value "C_CAP_1206")
      (footprint "eagle-import:C_1206")
      (libsource (lib "eagle-import") (part "C_CAP_1206"))
    )
    (comp (ref "C31")
      (value "C_CAP_1206")
      (footprint "eagle-import:C_1206")
      (libsource (lib "eagle-import") (part "C_CAP_1206"))
    )
    (comp (ref "C32")
      (value "C_CAP_1206")
      (footprint "eagle-import:C_1206")
      (libsource (lib "eagle-import") (part "C_CAP_1206"))
    )
    (comp (ref "C33")
      (value "C_CAP_1206")
      (footprint "eagle-import:C_1206")
      (libsource (lib "eagle-import") (part "C_CAP_1206"))
    )
    (comp (ref "C34")
      (value "C_CAP_1206")
      (footprint "eagle-import:C_1206")
      (libsource (lib "eagle-import") (part "C_CAP_1206"))
    )
    (comp (ref "C35")
      (value "C_CAP_1206")
      (footprint "eagle-import:C_1206")
      (libsource (lib "eagle-import") (part "C_CAP_1206"))
    )
    (comp (ref "C36")
      (value "C_CAP_1206")
      (footprint "eagle-import:C_1206")
      (libsource (lib "eagle-import") (part "C_CAP_1206"))
    )
    (comp (ref "C37")
      (value "C_CAP_1206")
      (footprint "eagle-import:C_1206")
      (libsource (lib "eagle-import") (part "C_CAP_1206"))
    )
    (comp (ref "C38")
      (value "C_CAP_1206")
      (footprint "eagle-import:C_1206")
      (libsource (lib "eagle-import") (part "C_CAP_1206"))
    )
    (comp (ref "C39")
      (value "C_CAP_1206")
      (footprint "eagle-import:C_1206")
      (libsource (lib "eagle-import") (part "C_CAP_1206"))
    )
    (comp (ref "C40")
      (value "C_CAP_1206")
      (footprint "eagle-import:C_1206")
      (libsource (lib "eagle-import") (part "C_CAP_1206"))
    )
    (comp (ref "C41")
      (value "C_CAP_1206")
      (footprint "eagle-import:C_1206")
      (libsource (lib "eagle-import") (part "C_CAP_1206"))
    )
    (comp (ref "C42")
      (value "C_CAP_1206")
      (footprint "eagle-import:C_1206")
      (libsource (lib "eagle-import") (part "C_CAP_1206"))
    )
    (comp (ref "C43")
      (value "C_CAP_1206")
      (footprint "eagle-import:C_1206")
      (libsource (lib "eagle-import") (part "C_CAP_1206"))
    )
    (comp (ref "C44")
      (value "C_CAP_1206")
      (footprint "eagle-import:C_1206")
      (libsource (lib "eagle-import") (part "C_CAP_1206"))
    )
    (comp (ref "C45")
      (value "C_CAP_1206")
      (footprint "eagle-import:C_1206")
      (libsource (lib "eagle-import") (part "C_CAP_1206"))
    )
    (comp (ref "C46")
      (value "C_CAP_1206")
      (footprint "eagle-import:C_1206")
      (libsource (lib "eagle-import") (part "C_CAP_1206"))
    )
    (comp (ref "C47")
      (value "C_CAP_1206")
      (footprint "eagle-import:C_1206")
      (libsource (lib "eagle-import") (part "C_CAP_1206"))
    )
    (comp (ref "Q1")
      (value "U_FDPF045N10A_TO-220F")
      (footprint "eagle-import:TO220F")
      (libsource (lib "eagle-import") (part "U_FDPF045N10A_TO-220F"))
    )
    (comp (ref "Q3")
      (value "U_FDPF045N10A_TO-220F")
      (footprint "eagle-import:TO220F")
      (libsource (lib "eagle-import") (part "U_FDPF045N10A_TO-220F"))
    )
    (comp (ref "Q4")
      (value "U_FDPF045N10A_TO-220F")
      (footprint "eagle-import:TO220F")
      (libsource (lib "eagle-import") (part "U_FDPF045N10A_TO-220F"))
    )
    (comp (ref "Q5")
      (value "U_FDPF045N10A_TO-220F")
      (footprint "eagle-import:TO220F")
      (libsource (lib "eagle-import") (part "U_FDPF045N10A_TO-220F"))
    )
    (comp (ref "Q6")
      (value "U_FDPF045N10A_TO-220F")
      (footprint "eagle-import:TO220F")
      (libsource (lib "eagle-import") (part "U_FDPF045N10A_TO-220F"))
    )
    (comp (ref "Q7")
      (value "U_FDPF045N10A_TO-220F")
      (footprint "eagle-import:TO220F")
      (libsource (lib "eagle-import") (part "U_FDPF045N10A_TO-220F"))
    )
    (comp (ref "R15")
      (value "R_RES_1206")
      (footprint "eagle-import:R_1206")
      (libsource (lib "eagle-import") (part "R_RES_1206"))
    )
    (comp (ref "R18")
      (value "R_RES_1206")
      (footprint "eagle-import:R_1206")
      (libsource (lib "eagle-import") (part "R_RES_1206"))
    )
    (comp (ref "R20")
      (value "R_RES_1206")
      (footprint "eagle-import:R_1206")
      (libsource (lib "eagle-import") (part "R_RES_1206"))
    )
    (comp (ref "R21")
      (value "R_RES_1206")
      (footprint "eagle-import:R_1206")
      (libsource (lib "eagle-import") (part "R_RES_1206"))
    )
    (comp (ref "R22")
      (value "R_RES_1206")
      (footprint "eagle-import:R_1206")
      (libsource (lib "eagle-import") (part "R_RES_1206"))
    )
    (comp (ref "R23")
      (value "R_RES_1206")
      (footprint "eagle-import:R_1206")
      (libsource (lib "eagle-import") (part "R_RES_1206"))
    )
    (comp (ref "U$11")
      (value "Q_MIC5021")
      (footprint "eagle-import:DIP8")
      (libsource (lib "eagle-import") (part "Q_MIC5021"))
    )
    (comp (ref "U$14")
      (value "J_1546074-2")
      (footprint "eagle-import:THERM_BLOCK_2")
      (libsource (lib "eagle-import") (part "J_1546074-2"))
    )
    (comp (ref "U$23")
      (value "Q_MIC5021")
      (footprint "eagle-import:DIP8")
      (libsource (lib "eagle-import") (part "Q_MIC5021"))
    )
    (comp (ref "U$26")
      (value "J_1546074-2")
      (footprint "eagle-import:THERM_BLOCK_2")
      (libsource (lib "eagle-import") (part "J_1546074-2"))
    )
    (comp (ref "U$27")
      (value "Q_MIC5021")
      (footprint "eagle-import:DIP8")
      (libsource (lib "eagle-import") (part "Q_MIC5021"))
    )
    (comp (ref "U$31")
      (value "J_1546074-2")
      (footprint "eagle-import:THERM_BLOCK_2")
      (libsource (lib "eagle-import") (part "J_1546074-2"))
    )
    (comp (ref "U$32")
      (value "Q_MIC5021")
      (footprint "eagle-import:DIP8")
      (libsource (lib "eagle-import") (part "Q_MIC5021"))
    )
    (comp (ref "U$36")
      (value "J_1546074-2")
      (footprint "eagle-import:THERM_BLOCK_2")
      (libsource (lib "eagle-import") (part "J_1546074-2"))
    )
    (comp (ref "U$37")
      (value "Q_MIC5021")
      (footprint "eagle-import:DIP8")
      (libsource (lib "eagle-import") (part "Q_MIC5021"))
    )
    (comp (ref "U$40")
      (value "J_1546074-2")
      (footprint "eagle-import:THERM_BLOCK_2")
      (libsource (lib "eagle-import") (part "J_1546074-2"))
    )
    (comp (ref "U$41")
      (value "Q_MIC5021")
      (footprint "eagle-import:DIP8")
      (libsource (lib "eagle-import") (part "Q_MIC5021"))
    )
    (comp (ref "U$44")
      (value "J_1546074-2")
      (footprint "eagle-import:THERM_BLOCK_2")
      (libsource (lib "eagle-import") (part "J_1546074-2"))
    )
    (comp (ref "U$45")
      (value "R_2512")
      (footprint "eagle-import:R_2512")
      (libsource (lib "eagle-import") (part "R_2512"))
    )
    (comp (ref "U$46")
      (value "R_2512")
      (footprint "eagle-import:R_2512")
      (libsource (lib "eagle-import") (part "R_2512"))
    )
    (comp (ref "U$47")
      (value "R_2512")
      (footprint "eagle-import:R_2512")
      (libsource (lib "eagle-import") (part "R_2512"))
    )
    (comp (ref "U$48")
      (value "R_2512")
      (footprint "eagle-import:R_2512")
      (libsource (lib "eagle-import") (part "R_2512"))
    )
    (comp (ref "U$49")
      (value "R_2512")
      (footprint "eagle-import:R_2512")
      (libsource (lib "eagle-import") (part "R_2512"))
    )
    (comp (ref "U$50")
      (value "R_2512")
      (footprint "eagle-import:R_2512")
      (libsource (lib "eagle-import") (part "R_2512"))
    )
    (comp (ref "C20")
      (value "C_CAP_1206")
      (footprint "eagle-import:C_1206")
      (libsource (lib "eagle-import") (part "C_CAP_1206"))
    )
    (comp (ref "C21")
      (value "C_CAP_1206")
      (footprint "eagle-import:C_1206")
      (libsource (lib "eagle-import") (part "C_CAP_1206"))
    )
    (comp (ref "C25")
      (value "C_CAP_1206")
      (footprint "eagle-import:C_1206")
      (libsource (lib "eagle-import") (part "C_CAP_1206"))
    )
    (comp (ref "C55")
      (value "C_CAP_1206")
      (footprint "eagle-import:C_1206")
      (libsource (lib "eagle-import") (part "C_CAP_1206"))
    )
    (comp (ref "C58")
      (value "1000uF")
      (footprint "eagle-import:C_10MM")
      (libsource (lib "eagle-import") (part "C_POL10MM"))
    )
    (comp (ref "C59")
      (value "C_POL10MM")
      (footprint "eagle-import:C_10MM")
      (libsource (lib "eagle-import") (part "C_POL10MM"))
    )
    (comp (ref "C60")
      (value "C_POL10MM")
      (footprint "eagle-import:C_10MM")
      (libsource (lib "eagle-import") (part "C_POL10MM"))
    )
    (comp (ref "C61")
      (value "C_POL10MM")
      (footprint "eagle-import:C_10MM")
      (libsource (lib "eagle-import") (part "C_POL10MM"))
    )
    (comp (ref "C62")
      (value "C_POL10MM")
      (footprint "eagle-import:C_10MM")
      (libsource (lib "eagle-import") (part "C_POL10MM"))
    )
    (comp (ref "C63")
      (value "C_POL10MM")
      (footprint "eagle-import:C_10MM")
      (libsource (lib "eagle-import") (part "C_POL10MM"))
    )
    (comp (ref "C64")
      (value "C_POL10MM")
      (footprint "eagle-import:C_10MM")
      (libsource (lib "eagle-import") (part "C_POL10MM"))
    )
    (comp (ref "C65")
      (value "C_POL10MM")
      (footprint "eagle-import:C_10MM")
      (libsource (lib "eagle-import") (part "C_POL10MM"))
    )
    (comp (ref "C66")
      (value "C_POL10MM")
      (footprint "eagle-import:C_10MM")
      (libsource (lib "eagle-import") (part "C_POL10MM"))
    )
    (comp (ref "C67")
      (value "C_POL10MM")
      (footprint "eagle-import:C_10MM")
      (libsource (lib "eagle-import") (part "C_POL10MM"))
    )
    (comp (ref "C75")
      (value "C_CAP_1206")
      (footprint "eagle-import:C_1206")
      (libsource (lib "eagle-import") (part "C_CAP_1206"))
    )
    (comp (ref "C76")
      (value "C_CAP_1206")
      (footprint "eagle-import:C_1206")
      (libsource (lib "eagle-import") (part "C_CAP_1206"))
    )
    (comp (ref "C77")
      (value "C_POL10MM")
      (footprint "eagle-import:C_10MM")
      (libsource (lib "eagle-import") (part "C_POL10MM"))
    )
    (comp (ref "C78")
      (value "C_POL10MM")
      (footprint "eagle-import:C_10MM")
      (libsource (lib "eagle-import") (part "C_POL10MM"))
    )
    (comp (ref "C79")
      (value "C_POL10MM")
      (footprint "eagle-import:C_10MM")
      (libsource (lib "eagle-import") (part "C_POL10MM"))
    )
    (comp (ref "D4")
      (value "1.5KE30C-RH")
      (footprint "eagle-import:DIODE_D3.5MM_LS15.24MM")
      (libsource (lib "eagle-import") (part "D_1.5KE480A_D3.5MM_LS15.24MM"))
    )
    (comp (ref "D5")
      (value "1.5KE30C-RH")
      (footprint "eagle-import:DIODE_D3.5MM_LS15.24MM")
      (libsource (lib "eagle-import") (part "D_1.5KE480A_D3.5MM_LS15.24MM"))
    )
    (comp (ref "D10")
      (value "1.5KE30C-RH")
      (footprint "eagle-import:DIODE_D3.5MM_LS15.24MM")
      (libsource (lib "eagle-import") (part "D_1.5KE480A_D3.5MM_LS15.24MM"))
    )
    (comp (ref "H1")
      (value "H_MNTHOLE_#8")
      (footprint "eagle-import:H_MNTHOLE_#8")
      (libsource (lib "eagle-import") (part "H_MNTHOLE_#8"))
    )
    (comp (ref "H2")
      (value "H_MNTHOLE_#8")
      (footprint "eagle-import:H_MNTHOLE_#8")
      (libsource (lib "eagle-import") (part "H_MNTHOLE_#8"))
    )
    (comp (ref "H3")
      (value "H_MNTHOLE_#8")
      (footprint "eagle-import:H_MNTHOLE_#8")
      (libsource (lib "eagle-import") (part "H_MNTHOLE_#8"))
    )
    (comp (ref "H4")
      (value "H_MNTHOLE_#8")
      (footprint "eagle-import:H_MNTHOLE_#8")
      (libsource (lib "eagle-import") (part "H_MNTHOLE_#8"))
    )
    (comp (ref "J2")
      (value "0399700102")
      (footprint "eagle-import:J_2CONHC")
      (libsource (lib "eagle-import") (part "J_0399700102"))
    )
    (comp (ref "P1")
      (value "TME1215S")
      (footprint "eagle-import:TME1215S")
      (libsource (lib "eagle-import") (part "TME1215S"))
    )
    (comp (ref "Q2")
      (value "Q_CSD18532KCSPCB")
      (footprint "eagle-import:TO-220-FLAT")
      (libsource (lib "eagle-import") (part "Q_CSD18532KCSPCB"))
    )
    (comp (ref "Q13")
      (value "Q_CSD18532KCSPCB")
      (footprint "eagle-import:TO-220-FLAT")
      (libsource (lib "eagle-import") (part "Q_CSD18532KCSPCB"))
    )
    (comp (ref "Q16")
      (value "IRS21851STR")
      (footprint "eagle-import:SOIC8")
      (libsource (lib "eagle-import") (part "Q_IRS21851STR"))
    )
    (comp (ref "Q17")
      (value "INA282")
      (footprint "eagle-import:SOIC8")
      (libsource (lib "eagle-import") (part "Q_INA28"))
    )
    (comp (ref "Q18")
      (value "Q_LDO")
      (footprint "eagle-import:TO-220")
      (libsource (lib "eagle-import") (part "Q_LDO"))
    )
    (comp (ref "R7")
      (value "0.001")
      (footprint "eagle-import:R_FC4L")
      (libsource (lib "eagle-import") (part "R_FC4L110R001JER"))
    )
    (comp (ref "R10")
      (value "R_RES_1206")
      (footprint "eagle-import:R_1206")
      (libsource (lib "eagle-import") (part "R_RES_1206"))
    )
    (comp (ref "R11")
      (value "R_1/4W")
      (footprint "eagle-import:R_1_4W")
      (libsource (lib "eagle-import") (part "R_1/4W"))
    )
    (comp (ref "R16")
      (value "R_RES_1206")
      (footprint "eagle-import:R_1206")
      (libsource (lib "eagle-import") (part "R_RES_1206"))
    )
    (comp (ref "R25")
      (value "R_1/4W")
      (footprint "eagle-import:R_1_4W")
      (libsource (lib "eagle-import") (part "R_1/4W"))
    )
    (comp (ref "R32")
      (value "R_RES_1206")
      (footprint "eagle-import:R_1206")
      (libsource (lib "eagle-import") (part "R_RES_1206"))
    )
  )
  (nets
    (net (code "1") (name "+12V") (class "Default")
      (node (ref "C21") (pin "2") (pinfunction "2_2") (pintype "passive"))
      (node (ref "C75") (pin "1") (pinfunction "1_1") (pintype "passive"))
      (node (ref "P1") (pin "2") (pinfunction "+VIN_2") (pintype "input"))
      (node (ref "Q16") (pin "1") (pinfunction "VCC_1") (pintype "bidirectional"))
      (node (ref "Q18") (pin "3") (pinfunction "VOUT_3") (pintype "bidirectional"))
    )
    (net (code "2") (name "GND") (class "Default")
      (node (ref "C1") (pin "1") (pinfunction "1_1") (pintype "passive"))
      (node (ref "C10") (pin "1") (pinfunction "1_1") (pintype "passive"))
      (node (ref "C11") (pin "2") (pinfunction "2_2") (pintype "passive"))
      (node (ref "C12") (pin "1") (pinfunction "1_1") (pintype "passive"))
      (node (ref "C13") (pin "2") (pinfunction "2_2") (pintype "passive"))
      (node (ref "C14") (pin "-") (pinfunction "-_-") (pintype "passive"))
      (node (ref "C15") (pin "-") (pinfunction "-_-") (pintype "passive"))
      (node (ref "C16") (pin "2") (pinfunction "2_2") (pintype "passive"))
      (node (ref "C17") (pin "-") (pinfunction "-_-") (pintype "passive"))
      (node (ref "C18") (pin "2") (pinfunction "2_2") (pintype "passive"))
      (node (ref "C19") (pin "1") (pinfunction "1_1") (pintype "passive"))
      (node (ref "C2") (pin "1") (pinfunction "1_1") (pintype "passive"))
      (node (ref "C20") (pin "2") (pinfunction "2_2") (pintype "passive"))
      (node (ref "C21") (pin "1") (pinfunction "1_1") (pintype "passive"))
      (node (ref "C22") (pin "-") (pinfunction "-_-") (pintype "passive"))
      (node (ref "C23") (pin "2") (pinfunction "2_2") (pintype "passive"))
      (node (ref "C24") (pin "1") (pinfunction "1_1") (pintype "passive"))
      (node (ref "C25") (pin "2") (pinfunction "2_2") (pintype "passive"))
      (node (ref "C26") (pin "-") (pinfunction "-_-") (pintype "passive"))
      (node (ref "C27") (pin "2") (pinfunction "2_2") (pintype "passive"))
      (node (ref "C28") (pin "1") (pinfunction "1_1") (pintype "passive"))
      (node (ref "C29") (pin "1") (pinfunction "1_1") (pintype "passive"))
      (node (ref "C3") (pin "1") (pinfunction "1_1") (pintype "passive"))
      (node (ref "C36") (pin "2") (pinfunction "2_2") (pintype "passive"))
      (node (ref "C37") (pin "2") (pinfunction "2_2") (pintype "passive"))
      (node (ref "C38") (pin "2") (pinfunction "2_2") (pintype "passive"))
      (node (ref "C39") (pin "2") (pinfunction "2_2") (pintype "passive"))
      (node (ref "C4") (pin "1") (pinfunction "1_1") (pintype "passive"))
      (node (ref "C40") (pin "2") (pinfunction "2_2") (pintype "passive"))
      (node (ref "C41") (pin "2") (pinfunction "2_2") (pintype "passive"))
      (node (ref "C42") (pin "2") (pinfunction "2_2") (pintype "passive"))
      (node (ref "C43") (pin "2") (pinfunction "2_2") (pintype "passive"))
      (node (ref "C44") (pin "2") (pinfunction "2_2") (pintype "passive"))
      (node (ref "C45") (pin "2") (pinfunction "2_2") (pintype "passive"))
      (node (ref "C46") (pin "2") (pinfunction "2_2") (pintype "passive"))
      (node (ref "C47") (pin "2") (pinfunction "2_2") (pintype "passive"))
      (node (ref "C49") (pin "2") (pinfunction "2_2") (pintype "passive"))
      (node (ref "C5") (pin "1") (pinfunction "1_1") (pintype "passive"))
      (node (ref "C50") (pin "2") (pinfunction "2_2") (pintype "passive"))
      (node (ref "C51") (pin "1") (pinfunction "1_1") (pintype "passive"))
      (node (ref "C52") (pin "2") (pinfunction "2_2") (pintype "passive"))
      (node (ref "C53") (pin "2") (pinfunction "2_2") (pintype "passive"))
      (node (ref "C54") (pin "2") (pinfunction "2_2") (pintype "passive"))
      (node (ref "C55") (pin "2") (pinfunction "2_2") (pintype "passive"))
      (node (ref "C56") (pin "-") (pinfunction "-_-") (pintype "passive"))
      (node (ref "C57") (pin "2") (pinfunction "2_2") (pintype "passive"))
      (node (ref "C58") (pin "P$2") (pinfunction "-_P$2") (pintype "passive"))
      (node (ref "C59") (pin "P$2") (pinfunction "-_P$2") (pintype "passive"))
      (node (ref "C6") (pin "1") (pinfunction "1_1") (pintype "passive"))
      (node (ref "C60") (pin "P$2") (pinfunction "-_P$2") (pintype "passive"))
      (node (ref "C61") (pin "P$2") (pinfunction "-_P$2") (pintype "passive"))
      (node (ref "C62") (pin "P$2") (pinfunction "-_P$2") (pintype "passive"))
      (node (ref "C63") (pin "P$2") (pinfunction "-_P$2") (pintype "passive"))
      (node (ref "C64") (pin "P$2") (pinfunction "-_P$2") (pintype "passive"))
      (node (ref "C65") (pin "P$2") (pinfunction "-_P$2") (pintype "passive"))
      (node (ref "C66") (pin "P$2") (pinfunction "-_P$2") (pintype "passive"))
      (node (ref "C67") (pin "P$2") (pinfunction "-_P$2") (pintype "passive"))
      (node (ref "C68") (pin "2") (pinfunction "2_2") (pintype "passive"))
      (node (ref "C69") (pin "2") (pinfunction "2_2") (pintype "passive"))
      (node (ref "C7") (pin "2") (pinfunction "2_2") (pintype "passive"))
      (node (ref "C70") (pin "2") (pinfunction "2_2") (pintype "passive"))
      (node (ref "C71") (pin "2") (pinfunction "2_2") (pintype "passive"))
      (node (ref "C72") (pin "2") (pinfunction "2_2") (pintype "passive"))
      (node (ref "C73") (pin "2") (pinfunction "2_2") (pintype "passive"))
      (node (ref "C74") (pin "2") (pinfunction "2_2") (pintype "passive"))
      (node (ref "C75") (pin "2") (pinfunction "2_2") (pintype "passive"))
      (node (ref "C77") (pin "P$2") (pinfunction "-_P$2") (pintype "passive"))
      (node (ref "C78") (pin "P$2") (pinfunction "-_P$2") (pintype "passive"))
      (node (ref "C79") (pin "P$2") (pinfunction "-_P$2") (pintype "passive"))
      (node (ref "C8") (pin "2") (pinfunction "2_2") (pintype "passive"))
      (node (ref "C9") (pin "1") (pinfunction "1_1") (pintype "passive"))
      (node (ref "D1") (pin "A") (pinfunction "A_A") (pintype "passive"))
      (node (ref "D10") (pin "A") (pinfunction "A_A") (pintype "passive"))
      (node (ref "D2") (pin "A") (pinfunction "A_A") (pintype "passive"))
      (node (ref "D3") (pin "A") (pinfunction "A_A") (pintype "passive"))
      (node (ref "D4") (pin "A") (pinfunction "A_A") (pintype "passive"))
      (node (ref "D5") (pin "A") (pinfunction "A_A") (pintype "passive"))
      (node (ref "D6") (pin "A") (pinfunction "A_A") (pintype "passive"))
      (node (ref "D7") (pin "A") (pinfunction "A_A") (pintype "passive"))
      (node (ref "J1") (pin "P$1") (pinfunction "1_P$1") (pintype "bidirectional"))
      (node (ref "J2") (pin "PIN2-1") (pinfunction "2-1_PIN2-1") (pintype "bidirectional"))
      (node (ref "J2") (pin "PIN2-2") (pinfunction "2-2_PIN2-2") (pintype "bidirectional"))
      (node (ref "J3") (pin "P$2") (pinfunction "P$2_P$2") (pintype "bidirectional"))
      (node (ref "J4") (pin "P$2") (pinfunction "P$2_P$2") (pintype "bidirectional"))
      (node (ref "J5") (pin "P$2") (pinfunction "P$2_P$2") (pintype "bidirectional"))
      (node (ref "J6") (pin "P$2") (pinfunction "P$2_P$2") (pintype "bidirectional"))
      (node (ref "J7") (pin "P$2") (pinfunction "P$2_P$2") (pintype "bidirectional"))
      (node (ref "J8") (pin "P$2") (pinfunction "P$2_P$2") (pintype "bidirectional"))
      (node (ref "JOLTEON-12V-1") (pin "1") (pinfunction "GND_1") (pintype "bidirectional"))
      (node (ref "JOLTEON-12V-1") (pin "7") (pinfunction "GND1_7") (pintype "bidirectional"))
      (node (ref "MAGNEMITE-12V-2") (pin "1") (pinfunction "GND_1") (pintype "bidirectional"))
      (node (ref "MAGNEMITE-12V-2") (pin "7") (pinfunction "GND1_7") (pintype "bidirectional"))
      (node (ref "N1") (pin "1-7") (pinfunction "7-DC--_1-7") (pintype "bidirectional"))
      (node (ref "N1") (pin "1-8") (pinfunction "8-DC-_1-8") (pintype "bidirectional"))
      (node (ref "N1") (pin "2-7") (pinfunction "7-DC--_2-7") (pintype "bidirectional"))
      (node (ref "N1") (pin "2-8") (pinfunction "8-DC-_2-8") (pintype "bidirectional"))
      (node (ref "N2") (pin "1-7") (pinfunction "7-DC--_1-7") (pintype "bidirectional"))
      (node (ref "N2") (pin "1-8") (pinfunction "8-DC-_1-8") (pintype "bidirectional"))
      (node (ref "N2") (pin "2-7") (pinfunction "7-DC--_2-7") (pintype "bidirectional"))
      (node (ref "N2") (pin "2-8") (pinfunction "8-DC-_2-8") (pintype "bidirectional"))
      (node (ref "N3") (pin "1-7") (pinfunction "7-DC--_1-7") (pintype "bidirectional"))
      (node (ref "N3") (pin "1-8") (pinfunction "8-DC-_1-8") (pintype "bidirectional"))
      (node (ref "N3") (pin "2-7") (pinfunction "7-DC--_2-7") (pintype "bidirectional"))
      (node (ref "N3") (pin "2-8") (pinfunction "8-DC-_2-8") (pintype "bidirectional"))
      (node (ref "N4") (pin "1-7") (pinfunction "7-DC--_1-7") (pintype "bidirectional"))
      (node (ref "N4") (pin "1-8") (pinfunction "8-DC-_1-8") (pintype "bidirectional"))
      (node (ref "N4") (pin "2-7") (pinfunction "7-DC--_2-7") (pintype "bidirectional"))
      (node (ref "N4") (pin "2-8") (pinfunction "8-DC-_2-8") (pintype "bidirectional"))
      (node (ref "N5") (pin "1-7") (pinfunction "7-DC--_1-7") (pintype "bidirectional"))
      (node (ref "N5") (pin "1-8") (pinfunction "8-DC-_1-8") (pintype "bidirectional"))
      (node (ref "N5") (pin "2-7") (pinfunction "7-DC--_2-7") (pintype "bidirectional"))
      (node (ref "N5") (pin "2-8") (pinfunction "8-DC-_2-8") (pintype "bidirectional"))
      (node (ref "N6") (pin "1-7") (pinfunction "7-DC--_1-7") (pintype "bidirectional"))
      (node (ref "N6") (pin "1-8") (pinfunction "8-DC-_1-8") (pintype "bidirectional"))
      (node (ref "N6") (pin "2-7") (pinfunction "7-DC--_2-7") (pintype "bidirectional"))
      (node (ref "N6") (pin "2-8") (pinfunction "8-DC-_2-8") (pintype "bidirectional"))
      (node (ref "N7") (pin "1-7") (pinfunction "7-DC--_1-7") (pintype "bidirectional"))
      (node (ref "N7") (pin "1-8") (pinfunction "8-DC-_1-8") (pintype "bidirectional"))
      (node (ref "N7") (pin "2-7") (pinfunction "7-DC--_2-7") (pintype "bidirectional"))
      (node (ref "N7") (pin "2-8") (pinfunction "8-DC-_2-8") (pintype "bidirectional"))
      (node (ref "N8") (pin "1-7") (pinfunction "7-DC--_1-7") (pintype "bidirectional"))
      (node (ref "N8") (pin "1-8") (pinfunction "8-DC-_1-8") (pintype "bidirectional"))
      (node (ref "N8") (pin "2-7") (pinfunction "7-DC--_2-7") (pintype "bidirectional"))
      (node (ref "N8") (pin "2-8") (pinfunction "8-DC-_2-8") (pintype "bidirectional"))
      (node (ref "P1") (pin "1") (pinfunction "-VIN_1") (pintype "input"))
      (node (ref "PICKACHU-5V") (pin "1") (pinfunction "GND_1") (pintype "bidirectional"))
      (node (ref "PICKACHU-5V") (pin "7") (pinfunction "GND1_7") (pintype "bidirectional"))
      (node (ref "Q10") (pin "1") (pinfunction "S_1") (pintype "bidirectional"))
      (node (ref "Q11") (pin "1") (pinfunction "S_1") (pintype "bidirectional"))
      (node (ref "Q12") (pin "1") (pinfunction "S_1") (pintype "bidirectional"))
      (node (ref "Q14") (pin "1") (pinfunction "S_1") (pintype "bidirectional"))
      (node (ref "Q16") (pin "4") (pinfunction "GND_4") (pintype "bidirectional"))
      (node (ref "Q17") (pin "2") (pinfunction "GND_2") (pintype "bidirectional"))
      (node (ref "Q17") (pin "7") (pinfunction "REF1_7") (pintype "bidirectional"))
      (node (ref "Q18") (pin "2") (pinfunction "GND_2") (pintype "bidirectional"))
      (node (ref "Q8") (pin "2") (pinfunction "GND_2") (pintype "bidirectional"))
      (node (ref "Q9") (pin "4") (pinfunction "GND_4") (pintype "bidirectional"))
      (node (ref "R10") (pin "1") (pinfunction "1_1") (pintype "passive"))
      (node (ref "R12") (pin "1") (pinfunction "1_1") (pintype "passive"))
      (node (ref "R2") (pin "1") (pinfunction "1_1") (pintype "passive"))
      (node (ref "R28") (pin "1") (pinfunction "1_1") (pintype "passive"))
      (node (ref "R3") (pin "1") (pinfunction "1_1") (pintype "passive"))
      (node (ref "R30") (pin "1") (pinfunction "1_1") (pintype "passive"))
      (node (ref "R31") (pin "1") (pinfunction "1_1") (pintype "passive"))
      (node (ref "R4") (pin "1") (pinfunction "1_1") (pintype "passive"))
      (node (ref "R5") (pin "1") (pinfunction "1_1") (pintype "passive"))
      (node (ref "RAICHU-5V-CRIT") (pin "1") (pinfunction "GND_1") (pintype "bidirectional"))
      (node (ref "RAICHU-5V-CRIT") (pin "7") (pinfunction "GND1_7") (pintype "bidirectional"))
      (node (ref "U$11") (pin "4") (pinfunction "GND_4") (pintype "bidirectional"))
      (node (ref "U$13") (pin "3") (pinfunction "GND_3") (pintype "bidirectional"))
      (node (ref "U$14") (pin "P$2") (pinfunction "P$2_P$2") (pintype "bidirectional"))
      (node (ref "U$23") (pin "4") (pinfunction "GND_4") (pintype "bidirectional"))
      (node (ref "U$26") (pin "P$2") (pinfunction "P$2_P$2") (pintype "bidirectional"))
      (node (ref "U$27") (pin "4") (pinfunction "GND_4") (pintype "bidirectional"))
      (node (ref "U$31") (pin "P$2") (pinfunction "P$2_P$2") (pintype "bidirectional"))
      (node (ref "U$32") (pin "4") (pinfunction "GND_4") (pintype "bidirectional"))
      (node (ref "U$36") (pin "P$2") (pinfunction "P$2_P$2") (pintype "bidirectional"))
      (node (ref "U$37") (pin "4") (pinfunction "GND_4") (pintype "bidirectional"))
      (node (ref "U$40") (pin "P$2") (pinfunction "P$2_P$2") (pintype "bidirectional"))
      (node (ref "U$41") (pin "4") (pinfunction "GND_4") (pintype "bidirectional"))
      (node (ref "U$44") (pin "P$2") (pinfunction "P$2_P$2") (pintype "bidirectional"))
      (node (ref "U$52") (pin "P$2") (pinfunction "P$2_P$2") (pintype "bidirectional"))
      (node (ref "U$53") (pin "P$2") (pinfunction "P$2_P$2") (pintype "bidirectional"))
      (node (ref "U$54") (pin "P$2") (pinfunction "P$2_P$2") (pintype "bidirectional"))
      (node (ref "U$55") (pin "P$2") (pinfunction "P$2_P$2") (pintype "bidirectional"))
      (node (ref "U$57") (pin "22") (pinfunction "GND1_22") (pintype "bidirectional"))
      (node (ref "U$57") (pin "8") (pinfunction "GND_8") (pintype "bidirectional"))
      (node (ref "U$64") (pin "7") (pinfunction "7-DC--_7") (pintype "bidirectional"))
      (node (ref "U$64") (pin "8") (pinfunction "8-DC-_8") (pintype "bidirectional"))
      (node (ref "U$70") (pin "4") (pinfunction "GND_4") (pintype "bidirectional"))
      (node (ref "U$72") (pin "P$2") (pinfunction "P$2_P$2") (pintype "bidirectional"))
      (node (ref "ZAPDOS-20V") (pin "1") (pinfunction "GND_1") (pintype "bidirectional"))
      (node (ref "ZAPDOS-20V") (pin "7") (pinfunction "GND1_7") (pintype "bidirectional"))
    )
    (net (code "3") (name "HIGHSIDE") (class "Default")
      (node (ref "C76") (pin "1") (pinfunction "1_1") (pintype "passive"))
      (node (ref "P1") (pin "4") (pinfunction "+VO_4") (pintype "output"))
      (node (ref "Q16") (pin "8") (pinfunction "VB_8") (pintype "bidirectional"))
    )
    (net (code "4") (name "IN+") (class "Default")
      (node (ref "Q17") (pin "1") (pinfunction "-IN_1") (pintype "bidirectional"))
      (node (ref "R7") (pin "SENSE1") (pinfunction "SENSE1_SENSE1") (pintype "bidirectional"))
    )
    (net (code "5") (name "IN-") (class "Default")
      (node (ref "Q17") (pin "8") (pinfunction "+IN_8") (pintype "bidirectional"))
      (node (ref "R7") (pin "SENSE2") (pinfunction "SENSE2_SENSE2") (pintype "bidirectional"))
    )
    (net (code "6") (name "MAINGATE") (class "Default")
      (node (ref "Q13") (pin "1") (pinfunction "G_1") (pintype "bidirectional"))
      (node (ref "Q2") (pin "1") (pinfunction "G_1") (pintype "bidirectional"))
      (node (ref "R32") (pin "1") (pinfunction "1_1") (pintype "passive"))
    )
    (net (code "7") (name "M_IMAIN") (class "Default")
      (node (ref "Q17") (pin "5") (pinfunction "OUT_5") (pintype "bidirectional"))
      (node (ref "U$57") (pin "28") (pinfunction "PC5_28") (pintype "bidirectional"))
    )
    (net (code "8") (name "M_V5-2") (class "Default")
      (node (ref "C52") (pin "1") (pinfunction "1_1") (pintype "passive"))
      (node (ref "R26") (pin "1") (pinfunction "1_1") (pintype "passive"))
      (node (ref "R28") (pin "2") (pinfunction "2_2") (pintype "passive"))
      (node (ref "U$57") (pin "24") (pinfunction "PC1_24") (pintype "bidirectional"))
    )
    (net (code "9") (name "M_V12-1") (class "Default")
      (node (ref "C53") (pin "1") (pinfunction "1_1") (pintype "passive"))
      (node (ref "R27") (pin "1") (pinfunction "1_1") (pintype "passive"))
      (node (ref "R30") (pin "2") (pinfunction "2_2") (pintype "passive"))
      (node (ref "U$57") (pin "25") (pinfunction "PC2_25") (pintype "bidirectional"))
    )
    (net (code "10") (name "M_V12-2") (class "Default")
      (node (ref "C54") (pin "1") (pinfunction "1_1") (pintype "passive"))
      (node (ref "R29") (pin "1") (pinfunction "1_1") (pintype "passive"))
      (node (ref "R31") (pin "2") (pinfunction "2_2") (pintype "passive"))
      (node (ref "U$57") (pin "26") (pinfunction "PC3_26") (pintype "bidirectional"))
    )
    (net (code "11") (name "M_VMAIN") (class "Default")
      (node (ref "C25") (pin "1") (pinfunction "1_1") (pintype "passive"))
      (node (ref "R10") (pin "2") (pinfunction "2_2") (pintype "passive"))
      (node (ref "R25") (pin "2") (pinfunction "2_2") (pintype "passive"))
      (node (ref "U$57") (pin "27") (pinfunction "PC4_27") (pintype "bidirectional"))
    )
    (net (code "12") (name "N$45") (class "Default")
      (node (ref "C76") (pin "2") (pinfunction "2_2") (pintype "passive"))
      (node (ref "P1") (pin "3") (pinfunction "-VO_3") (pintype "output"))
      (node (ref "Q13") (pin "3") (pinfunction "S_3") (pintype "bidirectional"))
      (node (ref "Q16") (pin "6") (pinfunction "VS_6") (pintype "bidirectional"))
      (node (ref "Q2") (pin "3") (pinfunction "S_3") (pintype "bidirectional"))
      (node (ref "R7") (pin "1") (pinfunction "1_1") (pintype "passive"))
    )
    (net (code "13") (name "Net-(D1-K)") (class "Default")
      (node (ref "C18") (pin "1") (pinfunction "1_1") (pintype "passive"))
      (node (ref "C73") (pin "1") (pinfunction "1_1") (pintype "passive"))
      (node (ref "D1") (pin "C") (pinfunction "K_C") (pintype "passive"))
      (node (ref "J6") (pin "P$1") (pinfunction "P$1_P$1") (pintype "bidirectional"))
      (node (ref "J7") (pin "P$1") (pinfunction "P$1_P$1") (pintype "bidirectional"))
      (node (ref "J8") (pin "P$1") (pinfunction "P$1_P$1") (pintype "bidirectional"))
      (node (ref "L6") (pin "5") (pinfunction "5_5") (pintype "bidirectional"))
      (node (ref "L6") (pin "6") (pinfunction "6_6") (pintype "bidirectional"))
      (node (ref "L6") (pin "7") (pinfunction "7_7") (pintype "bidirectional"))
      (node (ref "L6") (pin "8") (pinfunction "8_8") (pintype "bidirectional"))
    )
    (net (code "14") (name "Net-(D2-K)") (class "Default")
      (node (ref "C23") (pin "1") (pinfunction "1_1") (pintype "passive"))
      (node (ref "C74") (pin "1") (pinfunction "1_1") (pintype "passive"))
      (node (ref "D2") (pin "C") (pinfunction "K_C") (pintype "passive"))
      (node (ref "J3") (pin "P$1") (pinfunction "P$1_P$1") (pintype "bidirectional"))
      (node (ref "J4") (pin "P$1") (pinfunction "P$1_P$1") (pintype "bidirectional"))
      (node (ref "J5") (pin "P$1") (pinfunction "P$1_P$1") (pintype "bidirectional"))
      (node (ref "L8") (pin "5") (pinfunction "5_5") (pintype "bidirectional"))
      (node (ref "L8") (pin "6") (pinfunction "6_6") (pintype "bidirectional"))
      (node (ref "L8") (pin "7") (pinfunction "7_7") (pintype "bidirectional"))
      (node (ref "L8") (pin "8") (pinfunction "8_8") (pintype "bidirectional"))
    )
    (net (code "15") (name "Net-(D3-K)") (class "Default")
      (node (ref "C72") (pin "1") (pinfunction "1_1") (pintype "passive"))
      (node (ref "C8") (pin "1") (pinfunction "1_1") (pintype "passive"))
      (node (ref "D3") (pin "C") (pinfunction "K_C") (pintype "passive"))
      (node (ref "L4") (pin "5") (pinfunction "5_5") (pintype "bidirectional"))
      (node (ref "L4") (pin "6") (pinfunction "6_6") (pintype "bidirectional"))
      (node (ref "L4") (pin "7") (pinfunction "7_7") (pintype "bidirectional"))
      (node (ref "L4") (pin "8") (pinfunction "8_8") (pintype "bidirectional"))
      (node (ref "U$52") (pin "P$1") (pinfunction "P$1_P$1") (pintype "bidirectional"))
      (node (ref "U$53") (pin "P$1") (pinfunction "P$1_P$1") (pintype "bidirectional"))
    )
    (net (code "16") (name "Net-(D7-K)") (class "Default")
      (node (ref "C7") (pin "1") (pinfunction "1_1") (pintype "passive"))
      (node (ref "C71") (pin "1") (pinfunction "1_1") (pintype "passive"))
      (node (ref "D7") (pin "C") (pinfunction "K_C") (pintype "passive"))
      (node (ref "L3") (pin "5") (pinfunction "5_5") (pintype "bidirectional"))
      (node (ref "L3") (pin "6") (pinfunction "6_6") (pintype "bidirectional"))
      (node (ref "L3") (pin "7") (pinfunction "7_7") (pintype "bidirectional"))
      (node (ref "L3") (pin "8") (pinfunction "8_8") (pintype "bidirectional"))
      (node (ref "U$54") (pin "P$1") (pinfunction "P$1_P$1") (pintype "bidirectional"))
      (node (ref "U$55") (pin "P$1") (pinfunction "P$1_P$1") (pintype "bidirectional"))
    )
    (net (code "17") (name "Net-(J1-2)") (class "Default")
      (node (ref "J1") (pin "P$2") (pinfunction "2_P$2") (pintype "bidirectional"))
      (node (ref "R1") (pin "1") (pinfunction "1_1") (pintype "passive"))
      (node (ref "U$57") (pin "1") (pinfunction "PC6_1") (pintype "bidirectional"))
    )
    (net (code "18") (name "Net-(JOLTEON-12V-1-ADJUST)") (class "Default")
      (node (ref "JOLTEON-12V-1") (pin "4") (pinfunction "ADJUST_4") (pintype "bidirectional"))
      (node (ref "R5") (pin "2") (pinfunction "2_2") (pintype "passive"))
    )
    (net (code "19") (name "Net-(JOLTEON-12V-1-INHIBIT)") (class "Default")
      (node (ref "JOLTEON-12V-1") (pin "3") (pinfunction "INHIBIT_3") (pintype "bidirectional"))
      (node (ref "Q10") (pin "3") (pinfunction "D_3") (pintype "bidirectional"))
    )
    (net (code "20") (name "Net-(JOLTEON-12V-1-SENSE)") (class "Default")
      (node (ref "C22") (pin "+") (pinfunction "+_+") (pintype "passive"))
      (node (ref "JOLTEON-12V-1") (pin "5") (pinfunction "SENSE_5") (pintype "bidirectional"))
      (node (ref "JOLTEON-12V-1") (pin "6") (pinfunction "VOUT_6") (pintype "bidirectional"))
      (node (ref "L8") (pin "1") (pinfunction "1_1") (pintype "bidirectional"))
      (node (ref "L8") (pin "2") (pinfunction "2_2") (pintype "bidirectional"))
      (node (ref "L8") (pin "3") (pinfunction "3_3") (pintype "bidirectional"))
      (node (ref "L8") (pin "4") (pinfunction "4_4") (pintype "bidirectional"))
      (node (ref "R27") (pin "2") (pinfunction "2_2") (pintype "passive"))
    )
    (net (code "21") (name "Net-(JOLTEON-12V-1-VIN)") (class "Default")
      (node (ref "C2") (pin "2") (pinfunction "2_2") (pintype "passive"))
      (node (ref "JOLTEON-12V-1") (pin "2") (pinfunction "VIN_2") (pintype "bidirectional"))
      (node (ref "L7") (pin "5") (pinfunction "5_5") (pintype "bidirectional"))
      (node (ref "L7") (pin "6") (pinfunction "6_6") (pintype "bidirectional"))
      (node (ref "L7") (pin "7") (pinfunction "7_7") (pintype "bidirectional"))
      (node (ref "L7") (pin "8") (pinfunction "8_8") (pintype "bidirectional"))
    )
    (net (code "22") (name "Net-(MAGNEMITE-12V-2-ADJUST)") (class "Default")
      (node (ref "MAGNEMITE-12V-2") (pin "4") (pinfunction "ADJUST_4") (pintype "bidirectional"))
      (node (ref "R4") (pin "2") (pinfunction "2_2") (pintype "passive"))
    )
    (net (code "23") (name "Net-(MAGNEMITE-12V-2-INHIBIT)") (class "Default")
      (node (ref "MAGNEMITE-12V-2") (pin "3") (pinfunction "INHIBIT_3") (pintype "bidirectional"))
      (node (ref "Q12") (pin "3") (pinfunction "D_3") (pintype "bidirectional"))
    )
    (net (code "24") (name "Net-(MAGNEMITE-12V-2-SENSE)") (class "Default")
      (node (ref "C26") (pin "+") (pinfunction "+_+") (pintype "passive"))
      (node (ref "L6") (pin "1") (pinfunction "1_1") (pintype "bidirectional"))
      (node (ref "L6") (pin "2") (pinfunction "2_2") (pintype "bidirectional"))
      (node (ref "L6") (pin "3") (pinfunction "3_3") (pintype "bidirectional"))
      (node (ref "L6") (pin "4") (pinfunction "4_4") (pintype "bidirectional"))
      (node (ref "MAGNEMITE-12V-2") (pin "5") (pinfunction "SENSE_5") (pintype "bidirectional"))
      (node (ref "MAGNEMITE-12V-2") (pin "6") (pinfunction "VOUT_6") (pintype "bidirectional"))
      (node (ref "R29") (pin "2") (pinfunction "2_2") (pintype "passive"))
    )
    (net (code "25") (name "Net-(MAGNEMITE-12V-2-VIN)") (class "Default")
      (node (ref "C1") (pin "2") (pinfunction "2_2") (pintype "passive"))
      (node (ref "L5") (pin "5") (pinfunction "5_5") (pintype "bidirectional"))
      (node (ref "L5") (pin "6") (pinfunction "6_6") (pintype "bidirectional"))
      (node (ref "L5") (pin "7") (pinfunction "7_7") (pintype "bidirectional"))
      (node (ref "L5") (pin "8") (pinfunction "8_8") (pintype "bidirectional"))
      (node (ref "MAGNEMITE-12V-2") (pin "2") (pinfunction "VIN_2") (pintype "bidirectional"))
    )
    (net (code "26") (name "Net-(N1A-1-TRANS+)") (class "Default")
      (node (ref "N1") (pin "1-1") (pinfunction "1-TRANS+_1-1") (pintype "bidirectional"))
      (node (ref "N1") (pin "2-1") (pinfunction "1-TRANS+_2-1") (pintype "bidirectional"))
    )
    (net (code "27") (name "Net-(N1A-2-TRANS-)") (class "Default")
      (node (ref "N1") (pin "1-2") (pinfunction "2-TRANS-_1-2") (pintype "bidirectional"))
      (node (ref "N1") (pin "2-2") (pinfunction "2-TRANS-_2-2") (pintype "bidirectional"))
    )
    (net (code "28") (name "Net-(N1A-3+RECEIVE+)") (class "Default")
      (node (ref "N1") (pin "1-3") (pinfunction "3+RECEIVE+_1-3") (pintype "bidirectional"))
      (node (ref "N1") (pin "2-3") (pinfunction "3+RECEIVE+_2-3") (pintype "bidirectional"))
    )
    (net (code "29") (name "Net-(N1A-6-RECEIVE-)") (class "Default")
      (node (ref "N1") (pin "1-6") (pinfunction "6-RECEIVE-_1-6") (pintype "bidirectional"))
      (node (ref "N1") (pin "2-6") (pinfunction "6-RECEIVE-_2-6") (pintype "bidirectional"))
    )
    (net (code "30") (name "Net-(N2A-1-TRANS+)") (class "Default")
      (node (ref "N2") (pin "1-1") (pinfunction "1-TRANS+_1-1") (pintype "bidirectional"))
      (node (ref "N2") (pin "2-1") (pinfunction "1-TRANS+_2-1") (pintype "bidirectional"))
    )
    (net (code "31") (name "Net-(N2A-2-TRANS-)") (class "Default")
      (node (ref "N2") (pin "1-2") (pinfunction "2-TRANS-_1-2") (pintype "bidirectional"))
      (node (ref "N2") (pin "2-2") (pinfunction "2-TRANS-_2-2") (pintype "bidirectional"))
    )
    (net (code "32") (name "Net-(N2A-3+RECEIVE+)") (class "Default")
      (node (ref "N2") (pin "1-3") (pinfunction "3+RECEIVE+_1-3") (pintype "bidirectional"))
      (node (ref "N2") (pin "2-3") (pinfunction "3+RECEIVE+_2-3") (pintype "bidirectional"))
    )
    (net (code "33") (name "Net-(N2A-6-RECEIVE-)") (class "Default")
      (node (ref "N2") (pin "1-6") (pinfunction "6-RECEIVE-_1-6") (pintype "bidirectional"))
      (node (ref "N2") (pin "2-6") (pinfunction "6-RECEIVE-_2-6") (pintype "bidirectional"))
    )
    (net (code "34") (name "Net-(N3A-1-TRANS+)") (class "Default")
      (node (ref "N3") (pin "1-1") (pinfunction "1-TRANS+_1-1") (pintype "bidirectional"))
      (node (ref "N3") (pin "2-1") (pinfunction "1-TRANS+_2-1") (pintype "bidirectional"))
    )
    (net (code "35") (name "Net-(N3A-2-TRANS-)") (class "Default")
      (node (ref "N3") (pin "1-2") (pinfunction "2-TRANS-_1-2") (pintype "bidirectional"))
      (node (ref "N3") (pin "2-2") (pinfunction "2-TRANS-_2-2") (pintype "bidirectional"))
    )
    (net (code "36") (name "Net-(N3A-3+RECEIVE+)") (class "Default")
      (node (ref "N3") (pin "1-3") (pinfunction "3+RECEIVE+_1-3") (pintype "bidirectional"))
      (node (ref "N3") (pin "2-3") (pinfunction "3+RECEIVE+_2-3") (pintype "bidirectional"))
    )
    (net (code "37") (name "Net-(N3A-6-RECEIVE-)") (class "Default")
      (node (ref "N3") (pin "1-6") (pinfunction "6-RECEIVE-_1-6") (pintype "bidirectional"))
      (node (ref "N3") (pin "2-6") (pinfunction "6-RECEIVE-_2-6") (pintype "bidirectional"))
    )
    (net (code "38") (name "Net-(N4A-1-TRANS+)") (class "Default")
      (node (ref "N4") (pin "1-1") (pinfunction "1-TRANS+_1-1") (pintype "bidirectional"))
      (node (ref "N4") (pin "2-1") (pinfunction "1-TRANS+_2-1") (pintype "bidirectional"))
    )
    (net (code "39") (name "Net-(N4A-2-TRANS-)") (class "Default")
      (node (ref "N4") (pin "1-2") (pinfunction "2-TRANS-_1-2") (pintype "bidirectional"))
      (node (ref "N4") (pin "2-2") (pinfunction "2-TRANS-_2-2") (pintype "bidirectional"))
    )
    (net (code "40") (name "Net-(N4A-3+RECEIVE+)") (class "Default")
      (node (ref "N4") (pin "1-3") (pinfunction "3+RECEIVE+_1-3") (pintype "bidirectional"))
      (node (ref "N4") (pin "2-3") (pinfunction "3+RECEIVE+_2-3") (pintype "bidirectional"))
    )
    (net (code "41") (name "Net-(N4A-6-RECEIVE-)") (class "Default")
      (node (ref "N4") (pin "1-6") (pinfunction "6-RECEIVE-_1-6") (pintype "bidirectional"))
      (node (ref "N4") (pin "2-6") (pinfunction "6-RECEIVE-_2-6") (pintype "bidirectional"))
    )
    (net (code "42") (name "Net-(N5A-1-TRANS+)") (class "Default")
      (node (ref "N5") (pin "1-1") (pinfunction "1-TRANS+_1-1") (pintype "bidirectional"))
      (node (ref "N5") (pin "2-1") (pinfunction "1-TRANS+_2-1") (pintype "bidirectional"))
    )
    (net (code "43") (name "Net-(N5A-2-TRANS-)") (class "Default")
      (node (ref "N5") (pin "1-2") (pinfunction "2-TRANS-_1-2") (pintype "bidirectional"))
      (node (ref "N5") (pin "2-2") (pinfunction "2-TRANS-_2-2") (pintype "bidirectional"))
    )
    (net (code "44") (name "Net-(N5A-3+RECEIVE+)") (class "Default")
      (node (ref "N5") (pin "1-3") (pinfunction "3+RECEIVE+_1-3") (pintype "bidirectional"))
      (node (ref "N5") (pin "2-3") (pinfunction "3+RECEIVE+_2-3") (pintype "bidirectional"))
    )
    (net (code "45") (name "Net-(N5A-6-RECEIVE-)") (class "Default")
      (node (ref "N5") (pin "1-6") (pinfunction "6-RECEIVE-_1-6") (pintype "bidirectional"))
      (node (ref "N5") (pin "2-6") (pinfunction "6-RECEIVE-_2-6") (pintype "bidirectional"))
    )
    (net (code "46") (name "Net-(N6A-1-TRANS+)") (class "Default")
      (node (ref "N6") (pin "1-1") (pinfunction "1-TRANS+_1-1") (pintype "bidirectional"))
      (node (ref "N6") (pin "2-1") (pinfunction "1-TRANS+_2-1") (pintype "bidirectional"))
    )
    (net (code "47") (name "Net-(N6A-2-TRANS-)") (class "Default")
      (node (ref "N6") (pin "1-2") (pinfunction "2-TRANS-_1-2") (pintype "bidirectional"))
      (node (ref "N6") (pin "2-2") (pinfunction "2-TRANS-_2-2") (pintype "bidirectional"))
    )
    (net (code "48") (name "Net-(N6A-3+RECEIVE+)") (class "Default")
      (node (ref "N6") (pin "1-3") (pinfunction "3+RECEIVE+_1-3") (pintype "bidirectional"))
      (node (ref "N6") (pin "2-3") (pinfunction "3+RECEIVE+_2-3") (pintype "bidirectional"))
    )
    (net (code "49") (name "Net-(N6A-6-RECEIVE-)") (class "Default")
      (node (ref "N6") (pin "1-6") (pinfunction "6-RECEIVE-_1-6") (pintype "bidirectional"))
      (node (ref "N6") (pin "2-6") (pinfunction "6-RECEIVE-_2-6") (pintype "bidirectional"))
    )
    (net (code "50") (name "Net-(N7A-1-TRANS+)") (class "Default")
      (node (ref "N7") (pin "1-1") (pinfunction "1-TRANS+_1-1") (pintype "bidirectional"))
      (node (ref "N7") (pin "2-1") (pinfunction "1-TRANS+_2-1") (pintype "bidirectional"))
    )
    (net (code "51") (name "Net-(N7A-2-TRANS-)") (class "Default")
      (node (ref "N7") (pin "1-2") (pinfunction "2-TRANS-_1-2") (pintype "bidirectional"))
      (node (ref "N7") (pin "2-2") (pinfunction "2-TRANS-_2-2") (pintype "bidirectional"))
    )
    (net (code "52") (name "Net-(N7A-3+RECEIVE+)") (class "Default")
      (node (ref "N7") (pin "1-3") (pinfunction "3+RECEIVE+_1-3") (pintype "bidirectional"))
      (node (ref "N7") (pin "2-3") (pinfunction "3+RECEIVE+_2-3") (pintype "bidirectional"))
    )
    (net (code "53") (name "Net-(N7A-6-RECEIVE-)") (class "Default")
      (node (ref "N7") (pin "1-6") (pinfunction "6-RECEIVE-_1-6") (pintype "bidirectional"))
      (node (ref "N7") (pin "2-6") (pinfunction "6-RECEIVE-_2-6") (pintype "bidirectional"))
    )
    (net (code "54") (name "Net-(N8A-1-TRANS+)") (class "Default")
      (node (ref "N8") (pin "1-1") (pinfunction "1-TRANS+_1-1") (pintype "bidirectional"))
      (node (ref "N8") (pin "2-1") (pinfunction "1-TRANS+_2-1") (pintype "bidirectional"))
    )
    (net (code "55") (name "Net-(N8A-2-TRANS-)") (class "Default")
      (node (ref "N8") (pin "1-2") (pinfunction "2-TRANS-_1-2") (pintype "bidirectional"))
      (node (ref "N8") (pin "2-2") (pinfunction "2-TRANS-_2-2") (pintype "bidirectional"))
    )
    (net (code "56") (name "Net-(N8A-3+RECEIVE+)") (class "Default")
      (node (ref "N8") (pin "1-3") (pinfunction "3+RECEIVE+_1-3") (pintype "bidirectional"))
      (node (ref "N8") (pin "2-3") (pinfunction "3+RECEIVE+_2-3") (pintype "bidirectional"))
    )
    (net (code "57") (name "Net-(N8A-6-RECEIVE-)") (class "Default")
      (node (ref "N8") (pin "1-6") (pinfunction "6-RECEIVE-_1-6") (pintype "bidirectional"))
      (node (ref "N8") (pin "2-6") (pinfunction "6-RECEIVE-_2-6") (pintype "bidirectional"))
    )
    (net (code "58") (name "Net-(PICKACHU-5V-ADJUST)") (class "Default")
      (node (ref "PICKACHU-5V") (pin "4") (pinfunction "ADJUST_4") (pintype "bidirectional"))
      (node (ref "R2") (pin "2") (pinfunction "2_2") (pintype "passive"))
    )
    (net (code "59") (name "Net-(PICKACHU-5V-INHIBIT)") (class "Default")
      (node (ref "PICKACHU-5V") (pin "3") (pinfunction "INHIBIT_3") (pintype "bidirectional"))
      (node (ref "Q14") (pin "3") (pinfunction "D_3") (pintype "bidirectional"))
    )
    (net (code "60") (name "Net-(PICKACHU-5V-SENSE)") (class "Default")
      (node (ref "C14") (pin "+") (pinfunction "+_+") (pintype "passive"))
      (node (ref "L3") (pin "1") (pinfunction "1_1") (pintype "bidirectional"))
      (node (ref "L3") (pin "2") (pinfunction "2_2") (pintype "bidirectional"))
      (node (ref "L3") (pin "3") (pinfunction "3_3") (pintype "bidirectional"))
      (node (ref "L3") (pin "4") (pinfunction "4_4") (pintype "bidirectional"))
      (node (ref "PICKACHU-5V") (pin "5") (pinfunction "SENSE_5") (pintype "bidirectional"))
      (node (ref "PICKACHU-5V") (pin "6") (pinfunction "VOUT_6") (pintype "bidirectional"))
      (node (ref "R26") (pin "2") (pinfunction "2_2") (pintype "passive"))
    )
    (net (code "61") (name "Net-(PICKACHU-5V-VIN)") (class "Default")
      (node (ref "C3") (pin "2") (pinfunction "2_2") (pintype "passive"))
      (node (ref "L2") (pin "5") (pinfunction "5_5") (pintype "bidirectional"))
      (node (ref "L2") (pin "6") (pinfunction "6_6") (pintype "bidirectional"))
      (node (ref "L2") (pin "7") (pinfunction "7_7") (pintype "bidirectional"))
      (node (ref "L2") (pin "8") (pinfunction "8_8") (pintype "bidirectional"))
      (node (ref "PICKACHU-5V") (pin "2") (pinfunction "VIN_2") (pintype "bidirectional"))
    )
    (net (code "62") (name "Net-(Q1-G)") (class "Default")
      (node (ref "Q1") (pin "1") (pinfunction "G_1") (pintype "passive"))
      (node (ref "U$11") (pin "7") (pinfunction "GATE_7") (pintype "bidirectional"))
    )
    (net (code "63") (name "Net-(Q1-S)") (class "Default")
      (node (ref "Q1") (pin "3") (pinfunction "S_3") (pintype "passive"))
      (node (ref "U$11") (pin "5") (pinfunction "SENSE+_5") (pintype "bidirectional"))
      (node (ref "U$49") (pin "P$2") (pinfunction "2_P$2") (pintype "passive"))
    )
    (net (code "64") (name "Net-(Q3-G)") (class "Default")
      (node (ref "Q3") (pin "1") (pinfunction "G_1") (pintype "passive"))
      (node (ref "U$23") (pin "7") (pinfunction "GATE_7") (pintype "bidirectional"))
    )
    (net (code "65") (name "Net-(Q3-S)") (class "Default")
      (node (ref "Q3") (pin "3") (pinfunction "S_3") (pintype "passive"))
      (node (ref "U$23") (pin "5") (pinfunction "SENSE+_5") (pintype "bidirectional"))
      (node (ref "U$50") (pin "P$2") (pinfunction "2_P$2") (pintype "passive"))
    )
    (net (code "66") (name "Net-(Q4-G)") (class "Default")
      (node (ref "Q4") (pin "1") (pinfunction "G_1") (pintype "passive"))
      (node (ref "U$27") (pin "7") (pinfunction "GATE_7") (pintype "bidirectional"))
    )
    (net (code "67") (name "Net-(Q4-S)") (class "Default")
      (node (ref "Q4") (pin "3") (pinfunction "S_3") (pintype "passive"))
      (node (ref "U$27") (pin "5") (pinfunction "SENSE+_5") (pintype "bidirectional"))
      (node (ref "U$48") (pin "P$2") (pinfunction "2_P$2") (pintype "passive"))
    )
    (net (code "68") (name "Net-(Q5-G)") (class "Default")
      (node (ref "Q5") (pin "1") (pinfunction "G_1") (pintype "passive"))
      (node (ref "U$32") (pin "7") (pinfunction "GATE_7") (pintype "bidirectional"))
    )
    (net (code "69") (name "Net-(Q5-S)") (class "Default")
      (node (ref "Q5") (pin "3") (pinfunction "S_3") (pintype "passive"))
      (node (ref "U$32") (pin "5") (pinfunction "SENSE+_5") (pintype "bidirectional"))
      (node (ref "U$47") (pin "P$2") (pinfunction "2_P$2") (pintype "passive"))
    )
    (net (code "70") (name "Net-(Q6-G)") (class "Default")
      (node (ref "Q6") (pin "1") (pinfunction "G_1") (pintype "passive"))
      (node (ref "U$37") (pin "7") (pinfunction "GATE_7") (pintype "bidirectional"))
    )
    (net (code "71") (name "Net-(Q6-S)") (class "Default")
      (node (ref "Q6") (pin "3") (pinfunction "S_3") (pintype "passive"))
      (node (ref "U$37") (pin "5") (pinfunction "SENSE+_5") (pintype "bidirectional"))
      (node (ref "U$45") (pin "P$2") (pinfunction "2_P$2") (pintype "passive"))
    )
    (net (code "72") (name "Net-(Q7-G)") (class "Default")
      (node (ref "Q7") (pin "1") (pinfunction "G_1") (pintype "passive"))
      (node (ref "U$41") (pin "7") (pinfunction "GATE_7") (pintype "bidirectional"))
    )
    (net (code "73") (name "Net-(Q7-S)") (class "Default")
      (node (ref "Q7") (pin "3") (pinfunction "S_3") (pintype "passive"))
      (node (ref "U$41") (pin "5") (pinfunction "SENSE+_5") (pintype "bidirectional"))
      (node (ref "U$46") (pin "P$2") (pinfunction "2_P$2") (pintype "passive"))
    )
    (net (code "74") (name "Net-(Q9-A)") (class "Default")
      (node (ref "Q9") (pin "8") (pinfunction "A_8") (pintype "bidirectional"))
      (node (ref "R8") (pin "1") (pinfunction "1_1") (pintype "passive"))
      (node (ref "U$64") (pin "3") (pinfunction "3+RECEIVE+_3") (pintype "bidirectional"))
    )
    (net (code "75") (name "Net-(Q9-B)") (class "Default")
      (node (ref "Q9") (pin "7") (pinfunction "B_7") (pintype "bidirectional"))
      (node (ref "R8") (pin "2") (pinfunction "2_2") (pintype "passive"))
      (node (ref "U$64") (pin "6") (pinfunction "6-RECEIVE-_6") (pintype "bidirectional"))
    )
    (net (code "76") (name "Net-(Q9-D)") (class "Default")
      (node (ref "Q9") (pin "3") (pinfunction "D_3") (pintype "bidirectional"))
      (node (ref "U$57") (pin "3") (pinfunction "PD1_3") (pintype "bidirectional"))
    )
    (net (code "77") (name "Net-(Q9-R)") (class "Default")
      (node (ref "Q9") (pin "2") (pinfunction "R_2") (pintype "bidirectional"))
      (node (ref "U$57") (pin "2") (pinfunction "PD0_2") (pintype "bidirectional"))
    )
    (net (code "78") (name "Net-(Q9-Y)") (class "Default")
      (node (ref "Q9") (pin "5") (pinfunction "Y_5") (pintype "bidirectional"))
      (node (ref "R6") (pin "2") (pinfunction "2_2") (pintype "passive"))
      (node (ref "U$64") (pin "1") (pinfunction "1-TRANS+_1") (pintype "bidirectional"))
    )
    (net (code "79") (name "Net-(Q9-Z)") (class "Default")
      (node (ref "Q9") (pin "6") (pinfunction "Z_6") (pintype "bidirectional"))
      (node (ref "R6") (pin "1") (pinfunction "1_1") (pintype "passive"))
      (node (ref "U$64") (pin "2") (pinfunction "2-TRANS-_2") (pintype "bidirectional"))
    )
    (net (code "80") (name "Net-(Q10-G)") (class "Default")
      (node (ref "Q10") (pin "2") (pinfunction "G_2") (pintype "bidirectional"))
      (node (ref "R19") (pin "2") (pinfunction "2_2") (pintype "passive"))
    )
    (net (code "81") (name "Net-(Q11-D)") (class "Default")
      (node (ref "Q11") (pin "3") (pinfunction "D_3") (pintype "bidirectional"))
      (node (ref "ZAPDOS-20V") (pin "3") (pinfunction "INHIBIT_3") (pintype "bidirectional"))
    )
    (net (code "82") (name "Net-(Q11-G)") (class "Default")
      (node (ref "Q11") (pin "2") (pinfunction "G_2") (pintype "bidirectional"))
      (node (ref "R13") (pin "2") (pinfunction "2_2") (pintype "passive"))
    )
    (net (code "83") (name "Net-(Q12-G)") (class "Default")
      (node (ref "Q12") (pin "2") (pinfunction "G_2") (pintype "bidirectional"))
      (node (ref "R14") (pin "2") (pinfunction "2_2") (pintype "passive"))
    )
    (net (code "84") (name "Net-(Q14-G)") (class "Default")
      (node (ref "Q14") (pin "2") (pinfunction "G_2") (pintype "bidirectional"))
      (node (ref "R17") (pin "2") (pinfunction "2_2") (pintype "passive"))
    )
    (net (code "85") (name "Net-(Q15-G)") (class "Default")
      (node (ref "Q15") (pin "1") (pinfunction "G_1") (pintype "passive"))
      (node (ref "U$70") (pin "7") (pinfunction "GATE_7") (pintype "bidirectional"))
    )
    (net (code "86") (name "Net-(Q15-S)") (class "Default")
      (node (ref "Q15") (pin "3") (pinfunction "S_3") (pintype "passive"))
      (node (ref "U$70") (pin "5") (pinfunction "SENSE+_5") (pintype "bidirectional"))
      (node (ref "U$73") (pin "P$2") (pinfunction "2_P$2") (pintype "passive"))
    )
    (net (code "87") (name "Net-(Q16-HO)") (class "Default")
      (node (ref "Q16") (pin "7") (pinfunction "HO_7") (pintype "bidirectional"))
      (node (ref "R32") (pin "2") (pinfunction "2_2") (pintype "passive"))
    )
    (net (code "88") (name "Net-(Q16-IN)") (class "Default")
      (node (ref "Q16") (pin "2") (pinfunction "IN_2") (pintype "bidirectional"))
      (node (ref "R16") (pin "2") (pinfunction "2_2") (pintype "passive"))
    )
    (net (code "89") (name "Net-(Q17-REF2)") (class "Default")
      (node (ref "C20") (pin "1") (pinfunction "1_1") (pintype "passive"))
      (node (ref "Q17") (pin "3") (pinfunction "REF2_3") (pintype "bidirectional"))
      (node (ref "Q17") (pin "6") (pinfunction "V+_6") (pintype "bidirectional"))
      (node (ref "R11") (pin "1") (pinfunction "1_1") (pintype "passive"))
    )
    (net (code "90") (name "Net-(RAICHU-5V-CRIT-ADJUST)") (class "Default")
      (node (ref "R3") (pin "2") (pinfunction "2_2") (pintype "passive"))
      (node (ref "RAICHU-5V-CRIT") (pin "4") (pinfunction "ADJUST_4") (pintype "bidirectional"))
    )
    (net (code "91") (name "Net-(RAICHU-5V-CRIT-SENSE)") (class "Default")
      (node (ref "C15") (pin "+") (pinfunction "+_+") (pintype "passive"))
      (node (ref "L4") (pin "1") (pinfunction "1_1") (pintype "bidirectional"))
      (node (ref "L4") (pin "2") (pinfunction "2_2") (pintype "bidirectional"))
      (node (ref "L4") (pin "3") (pinfunction "3_3") (pintype "bidirectional"))
      (node (ref "L4") (pin "4") (pinfunction "4_4") (pintype "bidirectional"))
      (node (ref "RAICHU-5V-CRIT") (pin "5") (pinfunction "SENSE_5") (pintype "bidirectional"))
      (node (ref "RAICHU-5V-CRIT") (pin "6") (pinfunction "VOUT_6") (pintype "bidirectional"))
    )
    (net (code "92") (name "Net-(RAICHU-5V-CRIT-VIN)") (class "Default")
      (node (ref "C4") (pin "2") (pinfunction "2_2") (pintype "passive"))
      (node (ref "L1") (pin "5") (pinfunction "5_5") (pintype "bidirectional"))
      (node (ref "L1") (pin "6") (pinfunction "6_6") (pintype "bidirectional"))
      (node (ref "L1") (pin "7") (pinfunction "7_7") (pintype "bidirectional"))
      (node (ref "L1") (pin "8") (pinfunction "8_8") (pintype "bidirectional"))
      (node (ref "RAICHU-5V-CRIT") (pin "2") (pinfunction "VIN_2") (pintype "bidirectional"))
    )
    (net (code "93") (name "Net-(U$11-CT)") (class "Default")
      (node (ref "C41") (pin "1") (pinfunction "1_1") (pintype "passive"))
      (node (ref "U$11") (pin "3") (pinfunction "CT_3") (pintype "bidirectional"))
    )
    (net (code "94") (name "Net-(U$11-INPUT)") (class "Default")
      (node (ref "R18") (pin "2") (pinfunction "2_2") (pintype "passive"))
      (node (ref "U$11") (pin "2") (pinfunction "INPUT_2") (pintype "bidirectional"))
    )
    (net (code "95") (name "Net-(U$11-SENSE-)") (class "Default")
      (node (ref "U$11") (pin "6") (pinfunction "SENSE-_6") (pintype "bidirectional"))
      (node (ref "U$14") (pin "P$1") (pinfunction "P$1_P$1") (pintype "bidirectional"))
      (node (ref "U$49") (pin "P$1") (pinfunction "1_P$1") (pintype "passive"))
    )
    (net (code "96") (name "Net-(U$11-VBOOST)") (class "Default")
      (node (ref "C35") (pin "2") (pinfunction "2_2") (pintype "passive"))
      (node (ref "U$11") (pin "8") (pinfunction "VBOOST_8") (pintype "bidirectional"))
    )
    (net (code "97") (name "Net-(U$13-OUT)") (class "Default")
      (node (ref "U$13") (pin "2") (pinfunction "OUT_2") (pintype "bidirectional"))
      (node (ref "U$57") (pin "23") (pinfunction "PC0_23") (pintype "bidirectional"))
    )
    (net (code "98") (name "Net-(U$23-CT)") (class "Default")
      (node (ref "C37") (pin "1") (pinfunction "1_1") (pintype "passive"))
      (node (ref "U$23") (pin "3") (pinfunction "CT_3") (pintype "bidirectional"))
    )
    (net (code "99") (name "Net-(U$23-INPUT)") (class "Default")
      (node (ref "R23") (pin "2") (pinfunction "2_2") (pintype "passive"))
      (node (ref "U$23") (pin "2") (pinfunction "INPUT_2") (pintype "bidirectional"))
    )
    (net (code "100") (name "Net-(U$23-SENSE-)") (class "Default")
      (node (ref "U$23") (pin "6") (pinfunction "SENSE-_6") (pintype "bidirectional"))
      (node (ref "U$26") (pin "P$1") (pinfunction "P$1_P$1") (pintype "bidirectional"))
      (node (ref "U$50") (pin "P$1") (pinfunction "1_P$1") (pintype "passive"))
    )
    (net (code "101") (name "Net-(U$23-VBOOST)") (class "Default")
      (node (ref "C31") (pin "2") (pinfunction "2_2") (pintype "passive"))
      (node (ref "U$23") (pin "8") (pinfunction "VBOOST_8") (pintype "bidirectional"))
    )
    (net (code "102") (name "Net-(U$27-CT)") (class "Default")
      (node (ref "C40") (pin "1") (pinfunction "1_1") (pintype "passive"))
      (node (ref "U$27") (pin "3") (pinfunction "CT_3") (pintype "bidirectional"))
    )
    (net (code "103") (name "Net-(U$27-INPUT)") (class "Default")
      (node (ref "R15") (pin "2") (pinfunction "2_2") (pintype "passive"))
      (node (ref "U$27") (pin "2") (pinfunction "INPUT_2") (pintype "bidirectional"))
    )
    (net (code "104") (name "Net-(U$27-SENSE-)") (class "Default")
      (node (ref "U$27") (pin "6") (pinfunction "SENSE-_6") (pintype "bidirectional"))
      (node (ref "U$31") (pin "P$1") (pinfunction "P$1_P$1") (pintype "bidirectional"))
      (node (ref "U$48") (pin "P$1") (pinfunction "1_P$1") (pintype "passive"))
    )
    (net (code "105") (name "Net-(U$27-VBOOST)") (class "Default")
      (node (ref "C34") (pin "2") (pinfunction "2_2") (pintype "passive"))
      (node (ref "U$27") (pin "8") (pinfunction "VBOOST_8") (pintype "bidirectional"))
    )
    (net (code "106") (name "Net-(U$32-CT)") (class "Default")
      (node (ref "C36") (pin "1") (pinfunction "1_1") (pintype "passive"))
      (node (ref "U$32") (pin "3") (pinfunction "CT_3") (pintype "bidirectional"))
    )
    (net (code "107") (name "Net-(U$32-INPUT)") (class "Default")
      (node (ref "R22") (pin "2") (pinfunction "2_2") (pintype "passive"))
      (node (ref "U$32") (pin "2") (pinfunction "INPUT_2") (pintype "bidirectional"))
    )
    (net (code "108") (name "Net-(U$32-SENSE-)") (class "Default")
      (node (ref "U$32") (pin "6") (pinfunction "SENSE-_6") (pintype "bidirectional"))
      (node (ref "U$36") (pin "P$1") (pinfunction "P$1_P$1") (pintype "bidirectional"))
      (node (ref "U$47") (pin "P$1") (pinfunction "1_P$1") (pintype "passive"))
    )
    (net (code "109") (name "Net-(U$32-VBOOST)") (class "Default")
      (node (ref "C30") (pin "2") (pinfunction "2_2") (pintype "passive"))
      (node (ref "U$32") (pin "8") (pinfunction "VBOOST_8") (pintype "bidirectional"))
    )
    (net (code "110") (name "Net-(U$37-CT)") (class "Default")
      (node (ref "C39") (pin "1") (pinfunction "1_1") (pintype "passive"))
      (node (ref "U$37") (pin "3") (pinfunction "CT_3") (pintype "bidirectional"))
    )
    (net (code "111") (name "Net-(U$37-INPUT)") (class "Default")
      (node (ref "R20") (pin "2") (pinfunction "2_2") (pintype "passive"))
      (node (ref "U$37") (pin "2") (pinfunction "INPUT_2") (pintype "bidirectional"))
    )
    (net (code "112") (name "Net-(U$37-SENSE-)") (class "Default")
      (node (ref "U$37") (pin "6") (pinfunction "SENSE-_6") (pintype "bidirectional"))
      (node (ref "U$40") (pin "P$1") (pinfunction "P$1_P$1") (pintype "bidirectional"))
      (node (ref "U$45") (pin "P$1") (pinfunction "1_P$1") (pintype "passive"))
    )
    (net (code "113") (name "Net-(U$37-VBOOST)") (class "Default")
      (node (ref "C33") (pin "2") (pinfunction "2_2") (pintype "passive"))
      (node (ref "U$37") (pin "8") (pinfunction "VBOOST_8") (pintype "bidirectional"))
    )
    (net (code "114") (name "Net-(U$41-CT)") (class "Default")
      (node (ref "C38") (pin "1") (pinfunction "1_1") (pintype "passive"))
      (node (ref "U$41") (pin "3") (pinfunction "CT_3") (pintype "bidirectional"))
    )
    (net (code "115") (name "Net-(U$41-INPUT)") (class "Default")
      (node (ref "R21") (pin "2") (pinfunction "2_2") (pintype "passive"))
      (node (ref "U$41") (pin "2") (pinfunction "INPUT_2") (pintype "bidirectional"))
    )
    (net (code "116") (name "Net-(U$41-SENSE-)") (class "Default")
      (node (ref "U$41") (pin "6") (pinfunction "SENSE-_6") (pintype "bidirectional"))
      (node (ref "U$44") (pin "P$1") (pinfunction "P$1_P$1") (pintype "bidirectional"))
      (node (ref "U$46") (pin "P$1") (pinfunction "1_P$1") (pintype "passive"))
    )
    (net (code "117") (name "Net-(U$41-VBOOST)") (class "Default")
      (node (ref "C32") (pin "2") (pinfunction "2_2") (pintype "passive"))
      (node (ref "U$41") (pin "8") (pinfunction "VBOOST_8") (pintype "bidirectional"))
    )
    (net (code "118") (name "Net-(U$57-XTAL1)") (class "Default")
      (node (ref "C5") (pin "2") (pinfunction "2_2") (pintype "passive"))
      (node (ref "U$57") (pin "9") (pinfunction "XTAL1_9") (pintype "bidirectional"))
      (node (ref "X1") (pin "P$2") (pinfunction "2_P$2") (pintype "passive"))
    )
    (net (code "119") (name "Net-(U$57-XTAL2)") (class "Default")
      (node (ref "C6") (pin "2") (pinfunction "2_2") (pintype "passive"))
      (node (ref "U$57") (pin "10") (pinfunction "XTAL2_10") (pintype "bidirectional"))
      (node (ref "X1") (pin "P$1") (pinfunction "1_P$1") (pintype "passive"))
    )
    (net (code "120") (name "Net-(U$70-CT)") (class "Default")
      (node (ref "C49") (pin "1") (pinfunction "1_1") (pintype "passive"))
      (node (ref "U$70") (pin "3") (pinfunction "CT_3") (pintype "bidirectional"))
    )
    (net (code "121") (name "Net-(U$70-INPUT)") (class "Default")
      (node (ref "R24") (pin "2") (pinfunction "2_2") (pintype "passive"))
      (node (ref "U$70") (pin "2") (pinfunction "INPUT_2") (pintype "bidirectional"))
    )
    (net (code "122") (name "Net-(U$70-SENSE-)") (class "Default")
      (node (ref "U$70") (pin "6") (pinfunction "SENSE-_6") (pintype "bidirectional"))
      (node (ref "U$72") (pin "P$1") (pinfunction "P$1_P$1") (pintype "bidirectional"))
      (node (ref "U$73") (pin "P$1") (pinfunction "1_P$1") (pintype "passive"))
    )
    (net (code "123") (name "Net-(U$70-VBOOST)") (class "Default")
      (node (ref "C48") (pin "2") (pinfunction "2_2") (pintype "passive"))
      (node (ref "U$70") (pin "8") (pinfunction "VBOOST_8") (pintype "bidirectional"))
    )
    (net (code "124") (name "Net-(ZAPDOS-20V-ADJUST)") (class "Default")
      (node (ref "R12") (pin "2") (pinfunction "2_2") (pintype "passive"))
      (node (ref "ZAPDOS-20V") (pin "4") (pinfunction "ADJUST_4") (pintype "bidirectional"))
    )
    (net (code "125") (name "Net-(ZAPDOS-20V-SENSE)") (class "Default")
      (node (ref "C17") (pin "+") (pinfunction "+_+") (pintype "passive"))
      (node (ref "L10") (pin "1") (pinfunction "1_1") (pintype "bidirectional"))
      (node (ref "L10") (pin "2") (pinfunction "2_2") (pintype "bidirectional"))
      (node (ref "L10") (pin "3") (pinfunction "3_3") (pintype "bidirectional"))
      (node (ref "L10") (pin "4") (pinfunction "4_4") (pintype "bidirectional"))
      (node (ref "ZAPDOS-20V") (pin "5") (pinfunction "SENSE_5") (pintype "bidirectional"))
      (node (ref "ZAPDOS-20V") (pin "6") (pinfunction "VOUT_6") (pintype "bidirectional"))
    )
    (net (code "126") (name "Net-(ZAPDOS-20V-VIN)") (class "Default")
      (node (ref "C29") (pin "2") (pinfunction "2_2") (pintype "passive"))
      (node (ref "L9") (pin "5") (pinfunction "5_5") (pintype "bidirectional"))
      (node (ref "L9") (pin "6") (pinfunction "6_6") (pintype "bidirectional"))
      (node (ref "L9") (pin "7") (pinfunction "7_7") (pintype "bidirectional"))
      (node (ref "L9") (pin "8") (pinfunction "8_8") (pintype "bidirectional"))
      (node (ref "ZAPDOS-20V") (pin "2") (pinfunction "VIN_2") (pintype "bidirectional"))
    )
    (net (code "127") (name "S_12V-2") (class "Default")
      (node (ref "R14") (pin "1") (pinfunction "1_1") (pintype "passive"))
      (node (ref "U$57") (pin "6") (pinfunction "PD4_6") (pintype "bidirectional"))
    )
    (net (code "128") (name "S_MAIN") (class "Default")
      (node (ref "R16") (pin "1") (pinfunction "1_1") (pintype "passive"))
      (node (ref "U$57") (pin "4") (pinfunction "PD2_4") (pintype "bidirectional"))
    )
    (net (code "129") (name "S_MC1") (class "Default")
      (node (ref "R22") (pin "1") (pinfunction "1_1") (pintype "passive"))
      (node (ref "U$57") (pin "14") (pinfunction "PB0_14") (pintype "bidirectional"))
    )
    (net (code "130") (name "S_MC2") (class "Default")
      (node (ref "R21") (pin "1") (pinfunction "1_1") (pintype "passive"))
      (node (ref "U$57") (pin "13") (pinfunction "PD7_13") (pintype "bidirectional"))
    )
    (net (code "131") (name "S_MC3") (class "Default")
      (node (ref "R20") (pin "1") (pinfunction "1_1") (pintype "passive"))
      (node (ref "U$57") (pin "12") (pinfunction "PD6_12") (pintype "bidirectional"))
    )
    (net (code "132") (name "S_MC4") (class "Default")
      (node (ref "R18") (pin "1") (pinfunction "1_1") (pintype "passive"))
      (node (ref "U$57") (pin "11") (pinfunction "PD5_11") (pintype "bidirectional"))
    )
    (net (code "133") (name "S_MC5") (class "Default")
      (node (ref "R15") (pin "1") (pinfunction "1_1") (pintype "passive"))
      (node (ref "U$57") (pin "16") (pinfunction "PB2_16") (pintype "bidirectional"))
    )
    (net (code "134") (name "S_MC6") (class "Default")
      (node (ref "R23") (pin "1") (pinfunction "1_1") (pintype "passive"))
      (node (ref "U$57") (pin "17") (pinfunction "PB3_17") (pintype "bidirectional"))
    )
    (net (code "135") (name "S_POE") (class "Default")
      (node (ref "R13") (pin "1") (pinfunction "1_1") (pintype "passive"))
      (node (ref "U$57") (pin "5") (pinfunction "PD3_5") (pintype "bidirectional"))
    )
    (net (code "136") (name "S_V5-2") (class "Default")
      (node (ref "R17") (pin "1") (pinfunction "1_1") (pintype "passive"))
      (node (ref "U$57") (pin "18") (pinfunction "PB4_18") (pintype "bidirectional"))
    )
    (net (code "137") (name "S_V12-1") (class "Default")
      (node (ref "R19") (pin "1") (pinfunction "1_1") (pintype "passive"))
      (node (ref "U$57") (pin "19") (pinfunction "PB5_19") (pintype "bidirectional"))
    )
    (net (code "138") (name "S_V24AUX") (class "Default")
      (node (ref "R24") (pin "1") (pinfunction "1_1") (pintype "passive"))
      (node (ref "U$57") (pin "15") (pinfunction "PB1_15") (pintype "bidirectional"))
    )
    (net (code "139") (name "V1") (class "Default")
      (node (ref "C16") (pin "1") (pinfunction "1_1") (pintype "passive"))
      (node (ref "C55") (pin "1") (pinfunction "1_1") (pintype "passive"))
      (node (ref "D5") (pin "C") (pinfunction "K_C") (pintype "passive"))
      (node (ref "J2") (pin "PIN1-1") (pinfunction "1-1_PIN1-1") (pintype "bidirectional"))
      (node (ref "J2") (pin "PIN1-2") (pinfunction "1-2_PIN1-2") (pintype "bidirectional"))
      (node (ref "Q13") (pin "4") (pinfunction "P$1_4") (pintype "bidirectional"))
      (node (ref "Q18") (pin "1") (pinfunction "VIN_1") (pintype "bidirectional"))
      (node (ref "Q2") (pin "4") (pinfunction "P$1_4") (pintype "bidirectional"))
      (node (ref "Q8") (pin "1") (pinfunction "VIN_1") (pintype "bidirectional"))
      (node (ref "R25") (pin "1") (pinfunction "1_1") (pintype "passive"))
    )
    (net (code "140") (name "V24") (class "Default")
      (node (ref "C10") (pin "2") (pinfunction "2_2") (pintype "passive"))
      (node (ref "C19") (pin "2") (pinfunction "2_2") (pintype "passive"))
      (node (ref "C24") (pin "2") (pinfunction "2_2") (pintype "passive"))
      (node (ref "C28") (pin "2") (pinfunction "2_2") (pintype "passive"))
      (node (ref "C30") (pin "1") (pinfunction "1_1") (pintype "passive"))
      (node (ref "C31") (pin "1") (pinfunction "1_1") (pintype "passive"))
      (node (ref "C32") (pin "1") (pinfunction "1_1") (pintype "passive"))
      (node (ref "C33") (pin "1") (pinfunction "1_1") (pintype "passive"))
      (node (ref "C34") (pin "1") (pinfunction "1_1") (pintype "passive"))
      (node (ref "C35") (pin "1") (pinfunction "1_1") (pintype "passive"))
      (node (ref "C42") (pin "1") (pinfunction "1_1") (pintype "passive"))
      (node (ref "C43") (pin "1") (pinfunction "1_1") (pintype "passive"))
      (node (ref "C44") (pin "1") (pinfunction "1_1") (pintype "passive"))
      (node (ref "C45") (pin "1") (pinfunction "1_1") (pintype "passive"))
      (node (ref "C46") (pin "1") (pinfunction "1_1") (pintype "passive"))
      (node (ref "C47") (pin "1") (pinfunction "1_1") (pintype "passive"))
      (node (ref "C48") (pin "1") (pinfunction "1_1") (pintype "passive"))
      (node (ref "C50") (pin "1") (pinfunction "1_1") (pintype "passive"))
      (node (ref "C58") (pin "P$1") (pinfunction "+_P$1") (pintype "passive"))
      (node (ref "C59") (pin "P$1") (pinfunction "+_P$1") (pintype "passive"))
      (node (ref "C60") (pin "P$1") (pinfunction "+_P$1") (pintype "passive"))
      (node (ref "C61") (pin "P$1") (pinfunction "+_P$1") (pintype "passive"))
      (node (ref "C62") (pin "P$1") (pinfunction "+_P$1") (pintype "passive"))
      (node (ref "C63") (pin "P$1") (pinfunction "+_P$1") (pintype "passive"))
      (node (ref "C64") (pin "P$1") (pinfunction "+_P$1") (pintype "passive"))
      (node (ref "C65") (pin "P$1") (pinfunction "+_P$1") (pintype "passive"))
      (node (ref "C66") (pin "P$1") (pinfunction "+_P$1") (pintype "passive"))
      (node (ref "C67") (pin "P$1") (pinfunction "+_P$1") (pintype "passive"))
      (node (ref "C77") (pin "P$1") (pinfunction "+_P$1") (pintype "passive"))
      (node (ref "C78") (pin "P$1") (pinfunction "+_P$1") (pintype "passive"))
      (node (ref "C79") (pin "P$1") (pinfunction "+_P$1") (pintype "passive"))
      (node (ref "C9") (pin "2") (pinfunction "2_2") (pintype "passive"))
      (node (ref "D10") (pin "C") (pinfunction "K_C") (pintype "passive"))
      (node (ref "D4") (pin "C") (pinfunction "K_C") (pintype "passive"))
      (node (ref "L1") (pin "1") (pinfunction "1_1") (pintype "bidirectional"))
      (node (ref "L1") (pin "2") (pinfunction "2_2") (pintype "bidirectional"))
      (node (ref "L1") (pin "3") (pinfunction "3_3") (pintype "bidirectional"))
      (node (ref "L1") (pin "4") (pinfunction "4_4") (pintype "bidirectional"))
      (node (ref "L2") (pin "1") (pinfunction "1_1") (pintype "bidirectional"))
      (node (ref "L2") (pin "2") (pinfunction "2_2") (pintype "bidirectional"))
      (node (ref "L2") (pin "3") (pinfunction "3_3") (pintype "bidirectional"))
      (node (ref "L2") (pin "4") (pinfunction "4_4") (pintype "bidirectional"))
      (node (ref "L5") (pin "1") (pinfunction "1_1") (pintype "bidirectional"))
      (node (ref "L5") (pin "2") (pinfunction "2_2") (pintype "bidirectional"))
      (node (ref "L5") (pin "3") (pinfunction "3_3") (pintype "bidirectional"))
      (node (ref "L5") (pin "4") (pinfunction "4_4") (pintype "bidirectional"))
      (node (ref "L7") (pin "1") (pinfunction "1_1") (pintype "bidirectional"))
      (node (ref "L7") (pin "2") (pinfunction "2_2") (pintype "bidirectional"))
      (node (ref "L7") (pin "3") (pinfunction "3_3") (pintype "bidirectional"))
      (node (ref "L7") (pin "4") (pinfunction "4_4") (pintype "bidirectional"))
      (node (ref "L9") (pin "1") (pinfunction "1_1") (pintype "bidirectional"))
      (node (ref "L9") (pin "2") (pinfunction "2_2") (pintype "bidirectional"))
      (node (ref "L9") (pin "3") (pinfunction "3_3") (pintype "bidirectional"))
      (node (ref "L9") (pin "4") (pinfunction "4_4") (pintype "bidirectional"))
      (node (ref "Q1") (pin "2") (pinfunction "D_2") (pintype "passive"))
      (node (ref "Q15") (pin "2") (pinfunction "D_2") (pintype "passive"))
      (node (ref "Q3") (pin "2") (pinfunction "D_2") (pintype "passive"))
      (node (ref "Q4") (pin "2") (pinfunction "D_2") (pintype "passive"))
      (node (ref "Q5") (pin "2") (pinfunction "D_2") (pintype "passive"))
      (node (ref "Q6") (pin "2") (pinfunction "D_2") (pintype "passive"))
      (node (ref "Q7") (pin "2") (pinfunction "D_2") (pintype "passive"))
      (node (ref "R7") (pin "2") (pinfunction "2_2") (pintype "passive"))
      (node (ref "U$11") (pin "1") (pinfunction "VDD_1") (pintype "bidirectional"))
      (node (ref "U$23") (pin "1") (pinfunction "VDD_1") (pintype "bidirectional"))
      (node (ref "U$27") (pin "1") (pinfunction "VDD_1") (pintype "bidirectional"))
      (node (ref "U$32") (pin "1") (pinfunction "VDD_1") (pintype "bidirectional"))
      (node (ref "U$37") (pin "1") (pinfunction "VDD_1") (pintype "bidirectional"))
      (node (ref "U$41") (pin "1") (pinfunction "VDD_1") (pintype "bidirectional"))
      (node (ref "U$70") (pin "1") (pinfunction "VDD_1") (pintype "bidirectional"))
    )
    (net (code "141") (name "VA5") (class "Default")
      (node (ref "C11") (pin "1") (pinfunction "1_1") (pintype "passive"))
      (node (ref "C12") (pin "2") (pinfunction "2_2") (pintype "passive"))
      (node (ref "C13") (pin "1") (pinfunction "1_1") (pintype "passive"))
      (node (ref "C51") (pin "2") (pinfunction "2_2") (pintype "passive"))
      (node (ref "Q8") (pin "3") (pinfunction "VOUT_3") (pintype "bidirectional"))
      (node (ref "Q9") (pin "1") (pinfunction "VCC_1") (pintype "bidirectional"))
      (node (ref "R1") (pin "2") (pinfunction "2_2") (pintype "passive"))
      (node (ref "R11") (pin "2") (pinfunction "2_2") (pintype "passive"))
      (node (ref "U$13") (pin "1") (pinfunction "VIN_1") (pintype "bidirectional"))
      (node (ref "U$57") (pin "20") (pinfunction "AVCC_20") (pintype "bidirectional"))
      (node (ref "U$57") (pin "7") (pinfunction "VCC_7") (pintype "bidirectional"))
    )
    (net (code "142") (name "V_ANTENNA") (class "Default")
      (node (ref "C56") (pin "+") (pinfunction "+_+") (pintype "passive"))
      (node (ref "C57") (pin "1") (pinfunction "1_1") (pintype "passive"))
      (node (ref "D8") (pin "C") (pinfunction "K_C") (pintype "passive"))
      (node (ref "D9") (pin "C") (pinfunction "K_C") (pintype "passive"))
      (node (ref "N1") (pin "1-4") (pinfunction "4-DC+_1-4") (pintype "bidirectional"))
      (node (ref "N1") (pin "1-5") (pinfunction "5-DC++_1-5") (pintype "bidirectional"))
    )
    (net (code "143") (name "V_POE") (class "Default")
      (node (ref "C27") (pin "1") (pinfunction "1_1") (pintype "passive"))
      (node (ref "C68") (pin "1") (pinfunction "1_1") (pintype "passive"))
      (node (ref "C69") (pin "1") (pinfunction "1_1") (pintype "passive"))
      (node (ref "C70") (pin "1") (pinfunction "1_1") (pintype "passive"))
      (node (ref "D6") (pin "C") (pinfunction "K_C") (pintype "passive"))
      (node (ref "D8") (pin "A") (pinfunction "A_A") (pintype "passive"))
      (node (ref "L10") (pin "5") (pinfunction "5_5") (pintype "bidirectional"))
      (node (ref "L10") (pin "6") (pinfunction "6_6") (pintype "bidirectional"))
      (node (ref "L10") (pin "7") (pinfunction "7_7") (pintype "bidirectional"))
      (node (ref "L10") (pin "8") (pinfunction "8_8") (pintype "bidirectional"))
      (node (ref "N2") (pin "1-4") (pinfunction "4-DC+_1-4") (pintype "bidirectional"))
      (node (ref "N2") (pin "1-5") (pinfunction "5-DC++_1-5") (pintype "bidirectional"))
      (node (ref "N3") (pin "1-4") (pinfunction "4-DC+_1-4") (pintype "bidirectional"))
      (node (ref "N3") (pin "1-5") (pinfunction "5-DC++_1-5") (pintype "bidirectional"))
      (node (ref "N4") (pin "1-4") (pinfunction "4-DC+_1-4") (pintype "bidirectional"))
      (node (ref "N4") (pin "1-5") (pinfunction "5-DC++_1-5") (pintype "bidirectional"))
      (node (ref "N5") (pin "1-4") (pinfunction "4-DC+_1-4") (pintype "bidirectional"))
      (node (ref "N5") (pin "1-5") (pinfunction "5-DC++_1-5") (pintype "bidirectional"))
      (node (ref "N6") (pin "1-4") (pinfunction "4-DC+_1-4") (pintype "bidirectional"))
      (node (ref "N6") (pin "1-5") (pinfunction "5-DC++_1-5") (pintype "bidirectional"))
      (node (ref "N7") (pin "1-4") (pinfunction "4-DC+_1-4") (pintype "bidirectional"))
      (node (ref "N7") (pin "1-5") (pinfunction "5-DC++_1-5") (pintype "bidirectional"))
      (node (ref "N8") (pin "1-4") (pinfunction "4-DC+_1-4") (pintype "bidirectional"))
      (node (ref "N8") (pin "1-5") (pinfunction "5-DC++_1-5") (pintype "bidirectional"))
    )
    (net (code "144") (name "unconnected-(D9-PadA)") (class "Default")
      (node (ref "D9") (pin "A") (pinfunction "A_A") (pintype "passive"))
    )
    (net (code "145") (name "unconnected-(H1-Pad1)") (class "Default")
      (node (ref "H1") (pin "1") (pinfunction "1_1") (pintype "passive"))
    )
    (net (code "146") (name "unconnected-(H2-Pad1)") (class "Default")
      (node (ref "H2") (pin "1") (pinfunction "1_1") (pintype "passive"))
    )
    (net (code "147") (name "unconnected-(H3-Pad1)") (class "Default")
      (node (ref "H3") (pin "1") (pinfunction "1_1") (pintype "passive"))
    )
    (net (code "148") (name "unconnected-(H4-Pad1)") (class "Default")
      (node (ref "H4") (pin "1") (pinfunction "1_1") (pintype "passive"))
    )
    (net (code "149") (name "unconnected-(N1B-4-DC+-Pad2-4)") (class "Default")
      (node (ref "N1") (pin "2-4") (pinfunction "4-DC+_2-4") (pintype "bidirectional"))
    )
    (net (code "150") (name "unconnected-(N1B-5-DC++-Pad2-5)") (class "Default")
      (node (ref "N1") (pin "2-5") (pinfunction "5-DC++_2-5") (pintype "bidirectional"))
    )
    (net (code "151") (name "unconnected-(N2B-4-DC+-Pad2-4)") (class "Default")
      (node (ref "N2") (pin "2-4") (pinfunction "4-DC+_2-4") (pintype "bidirectional"))
    )
    (net (code "152") (name "unconnected-(N2B-5-DC++-Pad2-5)") (class "Default")
      (node (ref "N2") (pin "2-5") (pinfunction "5-DC++_2-5") (pintype "bidirectional"))
    )
    (net (code "153") (name "unconnected-(N3B-4-DC+-Pad2-4)") (class "Default")
      (node (ref "N3") (pin "2-4") (pinfunction "4-DC+_2-4") (pintype "bidirectional"))
    )
    (net (code "154") (name "unconnected-(N3B-5-DC++-Pad2-5)") (class "Default")
      (node (ref "N3") (pin "2-5") (pinfunction "5-DC++_2-5") (pintype "bidirectional"))
    )
    (net (code "155") (name "unconnected-(N4B-4-DC+-Pad2-4)") (class "Default")
      (node (ref "N4") (pin "2-4") (pinfunction "4-DC+_2-4") (pintype "bidirectional"))
    )
    (net (code "156") (name "unconnected-(N4B-5-DC++-Pad2-5)") (class "Default")
      (node (ref "N4") (pin "2-5") (pinfunction "5-DC++_2-5") (pintype "bidirectional"))
    )
    (net (code "157") (name "unconnected-(N5B-4-DC+-Pad2-4)") (class "Default")
      (node (ref "N5") (pin "2-4") (pinfunction "4-DC+_2-4") (pintype "bidirectional"))
    )
    (net (code "158") (name "unconnected-(N5B-5-DC++-Pad2-5)") (class "Default")
      (node (ref "N5") (pin "2-5") (pinfunction "5-DC++_2-5") (pintype "bidirectional"))
    )
    (net (code "159") (name "unconnected-(N6B-4-DC+-Pad2-4)") (class "Default")
      (node (ref "N6") (pin "2-4") (pinfunction "4-DC+_2-4") (pintype "bidirectional"))
    )
    (net (code "160") (name "unconnected-(N6B-5-DC++-Pad2-5)") (class "Default")
      (node (ref "N6") (pin "2-5") (pinfunction "5-DC++_2-5") (pintype "bidirectional"))
    )
    (net (code "161") (name "unconnected-(N7B-4-DC+-Pad2-4)") (class "Default")
      (node (ref "N7") (pin "2-4") (pinfunction "4-DC+_2-4") (pintype "bidirectional"))
    )
    (net (code "162") (name "unconnected-(N7B-5-DC++-Pad2-5)") (class "Default")
      (node (ref "N7") (pin "2-5") (pinfunction "5-DC++_2-5") (pintype "bidirectional"))
    )
    (net (code "163") (name "unconnected-(N8B-4-DC+-Pad2-4)") (class "Default")
      (node (ref "N8") (pin "2-4") (pinfunction "4-DC+_2-4") (pintype "bidirectional"))
    )
    (net (code "164") (name "unconnected-(N8B-5-DC++-Pad2-5)") (class "Default")
      (node (ref "N8") (pin "2-5") (pinfunction "5-DC++_2-5") (pintype "bidirectional"))
    )
    (net (code "165") (name "unconnected-(Q2-D-Pad2)") (class "Default")
      (node (ref "Q2") (pin "2") (pinfunction "D_2") (pintype "bidirectional"))
    )
    (net (code "166") (name "unconnected-(Q13-D-Pad2)") (class "Default")
      (node (ref "Q13") (pin "2") (pinfunction "D_2") (pintype "bidirectional"))
    )
    (net (code "167") (name "unconnected-(RAICHU-5V-CRIT-INHIBIT-Pad3)") (class "Default")
      (node (ref "RAICHU-5V-CRIT") (pin "3") (pinfunction "INHIBIT_3") (pintype "bidirectional"))
    )
    (net (code "168") (name "unconnected-(U$57-AREF-Pad21)") (class "Default")
      (node (ref "U$57") (pin "21") (pinfunction "AREF_21") (pintype "bidirectional"))
    )
    (net (code "169") (name "unconnected-(U$64-4-DC+-Pad4)") (class "Default")
      (node (ref "U$64") (pin "4") (pinfunction "4-DC+_4") (pintype "bidirectional"))
    )
    (net (code "170") (name "unconnected-(U$64-5-DC++-Pad5)") (class "Default")
      (node (ref "U$64") (pin "5") (pinfunction "5-DC++_5") (pintype "bidirectional"))
    )
  )
)
